# MainBoardSchematic.net
KiCad netlist of a schematic drawn in EAGLE
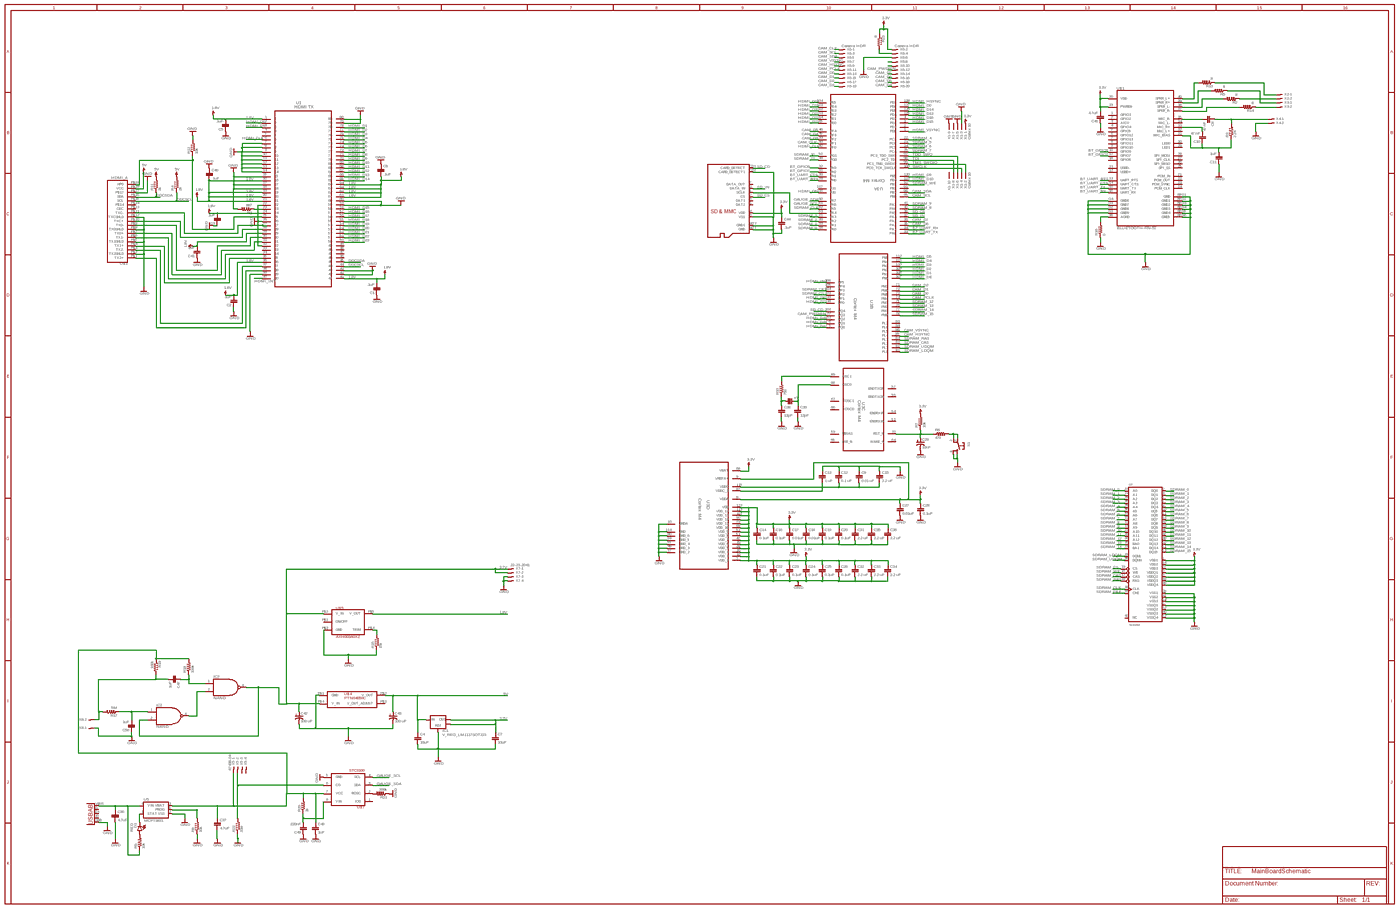
[diagram p0: schematic, sheet 1, overview]
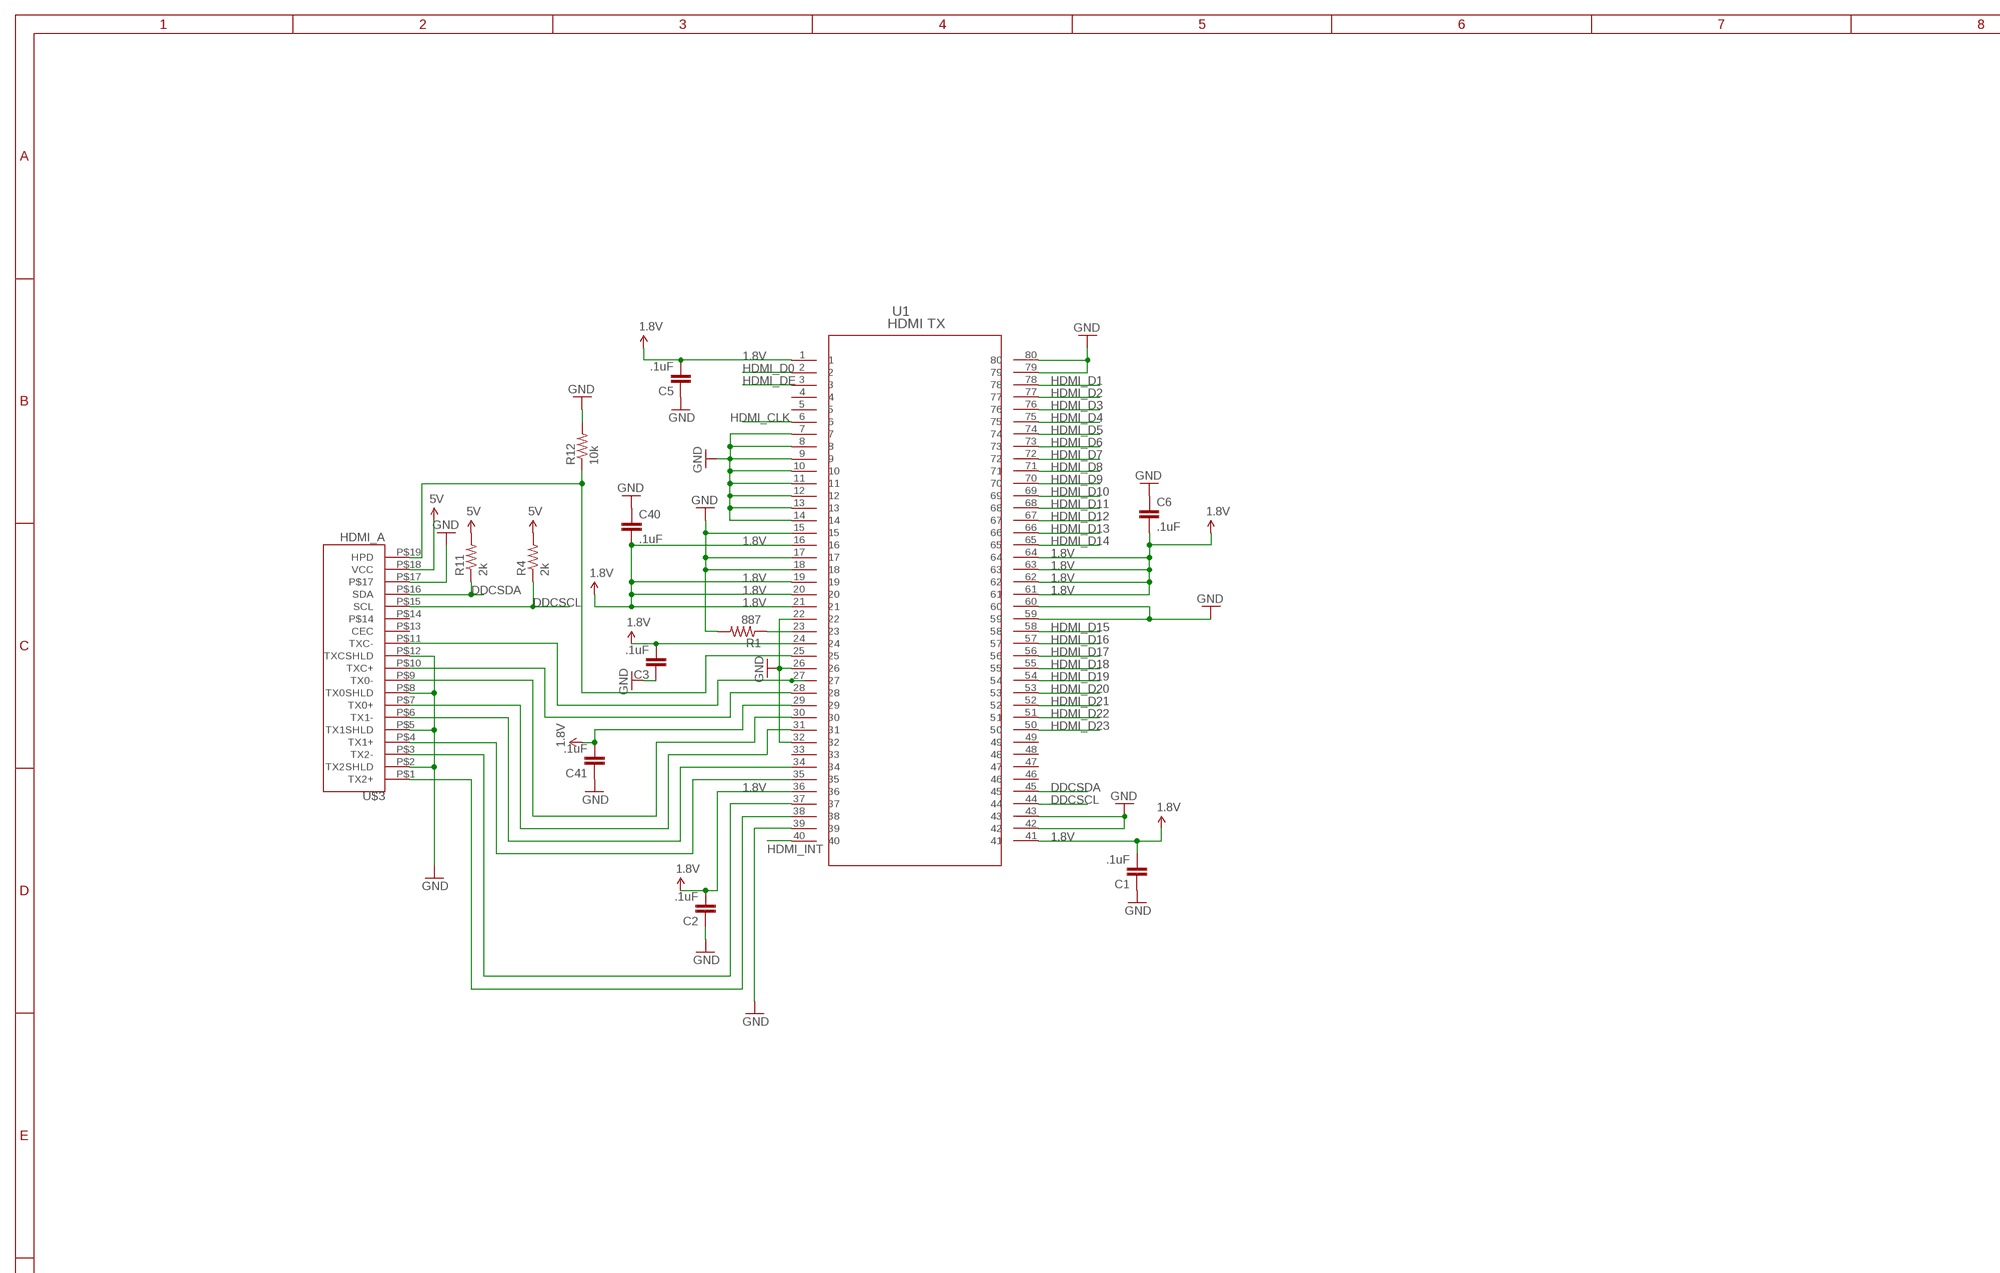
[diagram p1: schematic, sheet 1, part 1 of 4]
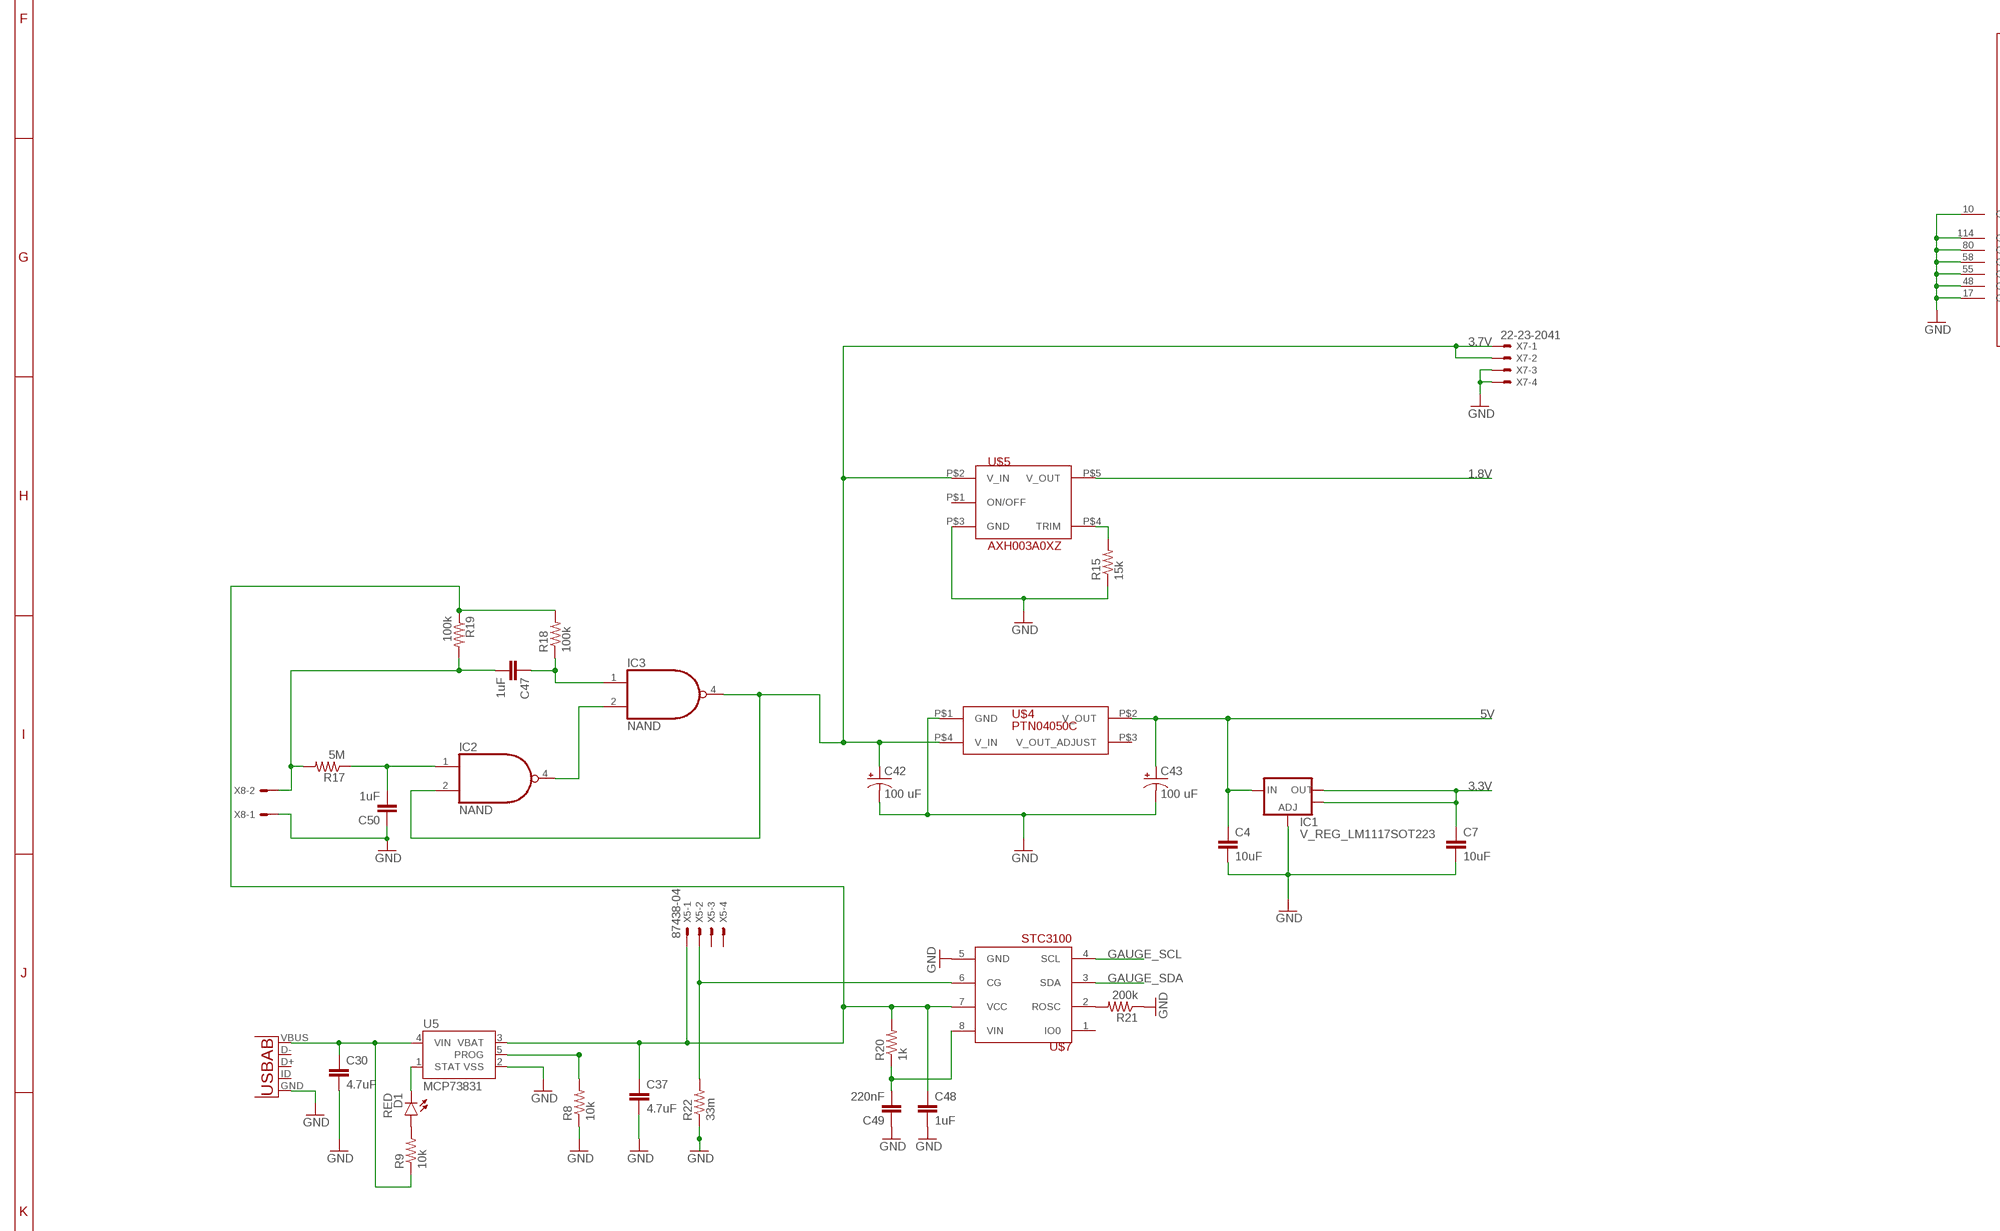
[diagram p2: schematic, sheet 1, part 2 of 4]
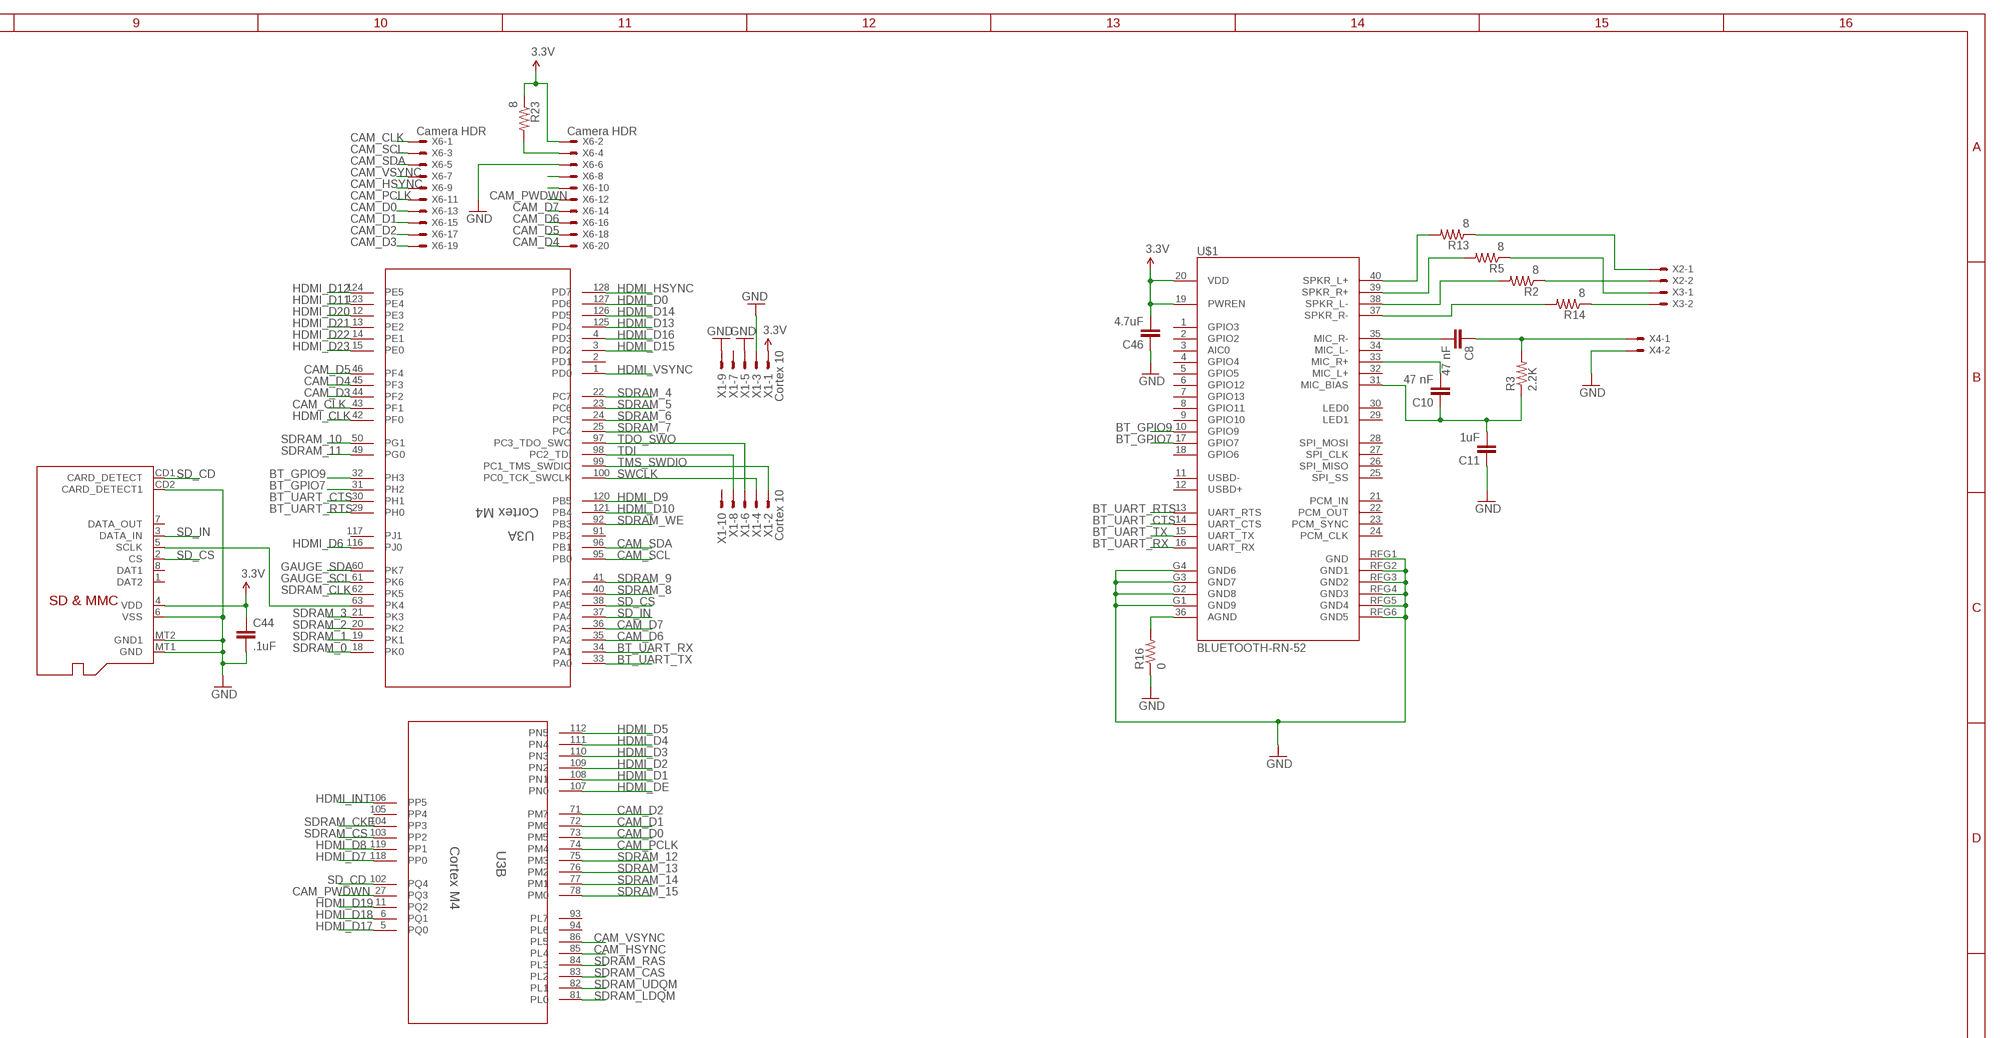
[diagram p3: schematic, sheet 1, part 3 of 4]
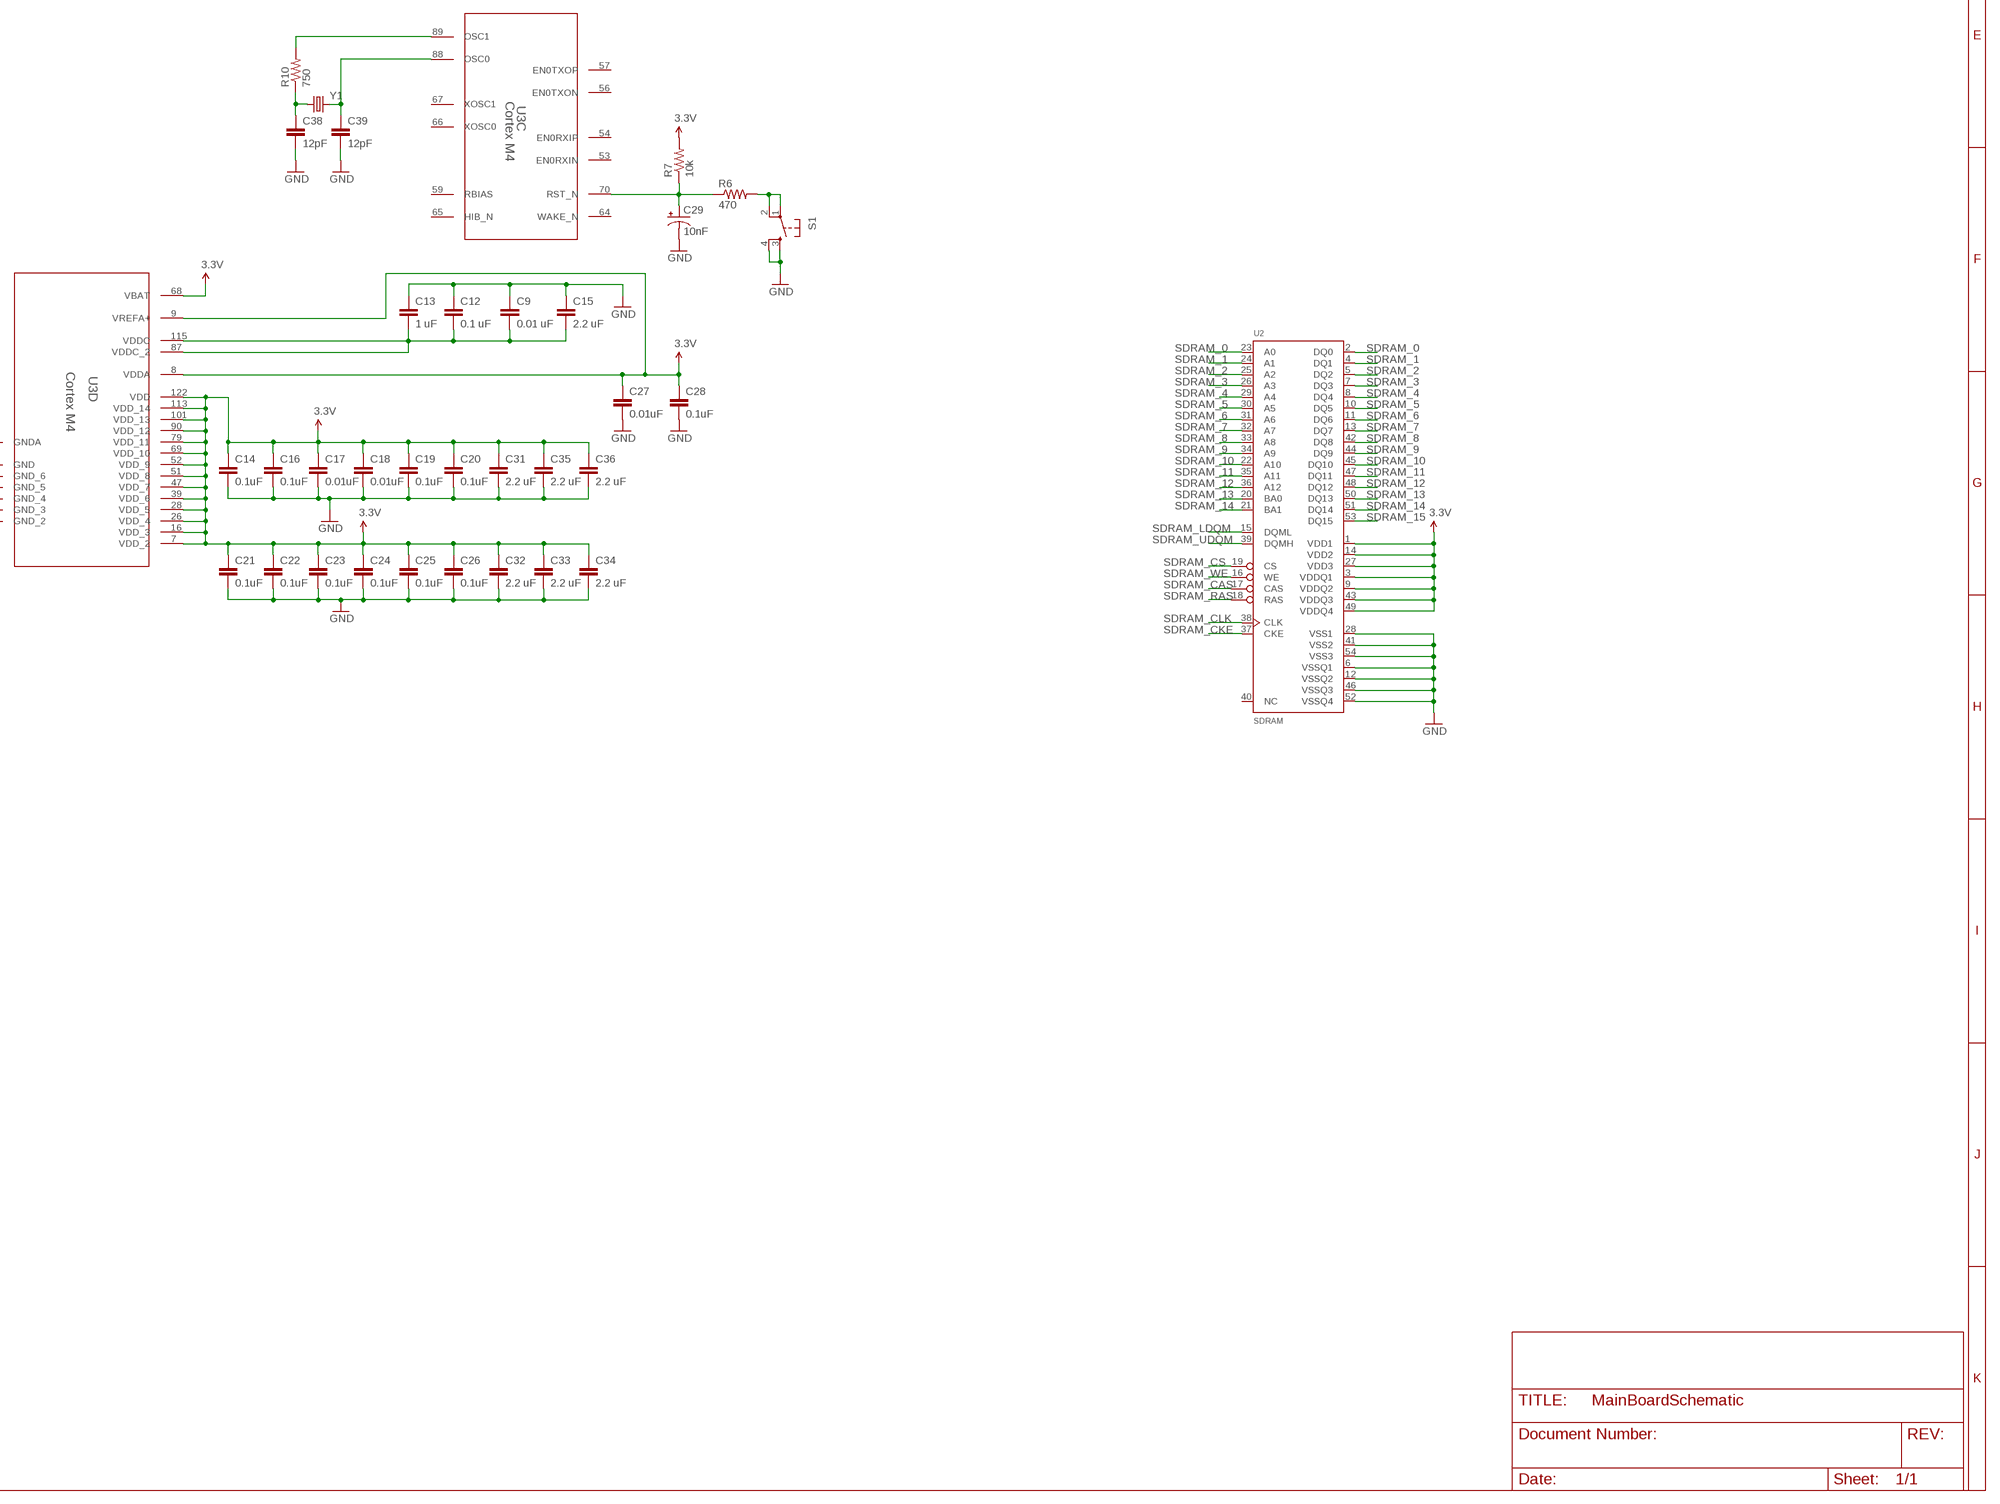
[diagram p4: schematic, sheet 1, part 4 of 4]

(export (version "E")
  (design (tool "Eeschema 10.0.6"))
  (components
    (comp (ref "C1")
      (value ".1uF")
      (footprint "eagle-import:0603-CAP")
      (libsource (lib "eagle-import") (part "CAP0603-CAP"))
    )
    (comp (ref "C2")
      (value ".1uF")
      (footprint "eagle-import:0603-CAP")
      (libsource (lib "eagle-import") (part "CAP0603-CAP"))
    )
    (comp (ref "C3")
      (value ".1uF")
      (footprint "eagle-import:0603-CAP")
      (libsource (lib "eagle-import") (part "CAP0603-CAP"))
    )
    (comp (ref "C4")
      (value "10uF")
      (footprint "eagle-import:0603-CAP")
      (libsource (lib "eagle-import") (part "CAP0603-CAP"))
    )
    (comp (ref "C5")
      (value ".1uF")
      (footprint "eagle-import:0603-CAP")
      (libsource (lib "eagle-import") (part "CAP0603-CAP"))
    )
    (comp (ref "C6")
      (value ".1uF")
      (footprint "eagle-import:0603-CAP")
      (libsource (lib "eagle-import") (part "CAP0603-CAP"))
    )
    (comp (ref "C7")
      (value "10uF")
      (footprint "eagle-import:0603-CAP")
      (libsource (lib "eagle-import") (part "CAP0603-CAP"))
    )
    (comp (ref "C8")
      (value "47 nF")
      (footprint "eagle-import:0603-CAP")
      (libsource (lib "eagle-import") (part "CAP0603-CAP"))
    )
    (comp (ref "C9")
      (value "0.01 uF")
      (footprint "eagle-import:0603-CAP")
      (libsource (lib "eagle-import") (part "CAP0603-CAP"))
    )
    (comp (ref "C10")
      (value "47 nF")
      (footprint "eagle-import:0603-CAP")
      (libsource (lib "eagle-import") (part "CAP0603-CAP"))
    )
    (comp (ref "C11")
      (value "1uF")
      (footprint "eagle-import:0603-CAP")
      (libsource (lib "eagle-import") (part "CAP0603-CAP"))
    )
    (comp (ref "C12")
      (value "0.1 uF")
      (footprint "eagle-import:0603-CAP")
      (libsource (lib "eagle-import") (part "CAP0603-CAP"))
    )
    (comp (ref "C13")
      (value "1 uF")
      (footprint "eagle-import:0603-CAP")
      (libsource (lib "eagle-import") (part "CAP0603-CAP"))
    )
    (comp (ref "C14")
      (value "0.1uF")
      (footprint "eagle-import:0603-CAP")
      (libsource (lib "eagle-import") (part "CAP0603-CAP"))
    )
    (comp (ref "C15")
      (value "2.2 uF")
      (footprint "eagle-import:0603-CAP")
      (libsource (lib "eagle-import") (part "CAP0603-CAP"))
    )
    (comp (ref "C16")
      (value "0.1uF")
      (footprint "eagle-import:0603-CAP")
      (libsource (lib "eagle-import") (part "CAP0603-CAP"))
    )
    (comp (ref "C17")
      (value "0.01uF")
      (footprint "eagle-import:0603-CAP")
      (libsource (lib "eagle-import") (part "CAP0603-CAP"))
    )
    (comp (ref "C18")
      (value "0.01uF")
      (footprint "eagle-import:0603-CAP")
      (libsource (lib "eagle-import") (part "CAP0603-CAP"))
    )
    (comp (ref "C19")
      (value "0.1uF")
      (footprint "eagle-import:0603-CAP")
      (libsource (lib "eagle-import") (part "CAP0603-CAP"))
    )
    (comp (ref "C20")
      (value "0.1uF")
      (footprint "eagle-import:0603-CAP")
      (libsource (lib "eagle-import") (part "CAP0603-CAP"))
    )
    (comp (ref "C21")
      (value "0.1uF")
      (footprint "eagle-import:0603-CAP")
      (libsource (lib "eagle-import") (part "CAP0603-CAP"))
    )
    (comp (ref "C22")
      (value "0.1uF")
      (footprint "eagle-import:0603-CAP")
      (libsource (lib "eagle-import") (part "CAP0603-CAP"))
    )
    (comp (ref "C23")
      (value "0.1uF")
      (footprint "eagle-import:0603-CAP")
      (libsource (lib "eagle-import") (part "CAP0603-CAP"))
    )
    (comp (ref "C24")
      (value "0.1uF")
      (footprint "eagle-import:0603-CAP")
      (libsource (lib "eagle-import") (part "CAP0603-CAP"))
    )
    (comp (ref "C25")
      (value "0.1uF")
      (footprint "eagle-import:0603-CAP")
      (libsource (lib "eagle-import") (part "CAP0603-CAP"))
    )
    (comp (ref "C26")
      (value "0.1uF")
      (footprint "eagle-import:0603-CAP")
      (libsource (lib "eagle-import") (part "CAP0603-CAP"))
    )
    (comp (ref "C27")
      (value "0.01uF")
      (footprint "eagle-import:0603-CAP")
      (libsource (lib "eagle-import") (part "CAP0603-CAP"))
    )
    (comp (ref "C28")
      (value "0.1uF")
      (footprint "eagle-import:0603-CAP")
      (libsource (lib "eagle-import") (part "CAP0603-CAP"))
    )
    (comp (ref "C29")
      (value "10nF")
      (footprint "eagle-import:EIA6032")
      (libsource (lib "eagle-import") (part "SparkFun-Passives_CAP_POL6032"))
    )
    (comp (ref "C30")
      (value "4.7uF")
      (footprint "eagle-import:0603-CAP")
      (libsource (lib "eagle-import") (part "CAP0603-CAP"))
    )
    (comp (ref "C31")
      (value "2.2 uF")
      (footprint "eagle-import:0603-CAP")
      (libsource (lib "eagle-import") (part "CAP0603-CAP"))
    )
    (comp (ref "C32")
      (value "2.2 uF")
      (footprint "eagle-import:0603-CAP")
      (libsource (lib "eagle-import") (part "CAP0603-CAP"))
    )
    (comp (ref "C33")
      (value "2.2 uF")
      (footprint "eagle-import:0603-CAP")
      (libsource (lib "eagle-import") (part "CAP0603-CAP"))
    )
    (comp (ref "C34")
      (value "2.2 uF")
      (footprint "eagle-import:0603-CAP")
      (libsource (lib "eagle-import") (part "CAP0603-CAP"))
    )
    (comp (ref "C35")
      (value "2.2 uF")
      (footprint "eagle-import:0603-CAP")
      (libsource (lib "eagle-import") (part "CAP0603-CAP"))
    )
    (comp (ref "C36")
      (value "2.2 uF")
      (footprint "eagle-import:0603-CAP")
      (libsource (lib "eagle-import") (part "CAP0603-CAP"))
    )
    (comp (ref "C37")
      (value "4.7uF")
      (footprint "eagle-import:0603-CAP")
      (libsource (lib "eagle-import") (part "CAP0603-CAP"))
    )
    (comp (ref "C38")
      (value "12pF")
      (footprint "eagle-import:0603-CAP")
      (libsource (lib "eagle-import") (part "CAP0603-CAP"))
    )
    (comp (ref "C39")
      (value "12pF")
      (footprint "eagle-import:0603-CAP")
      (libsource (lib "eagle-import") (part "CAP0603-CAP"))
    )
    (comp (ref "C40")
      (value ".1uF")
      (footprint "eagle-import:0603-CAP")
      (libsource (lib "eagle-import") (part "CAP0603-CAP"))
    )
    (comp (ref "C41")
      (value ".1uF")
      (footprint "eagle-import:0603-CAP")
      (libsource (lib "eagle-import") (part "CAP0603-CAP"))
    )
    (comp (ref "C42")
      (value "100 uF")
      (footprint "eagle-import:EIA6032")
      (libsource (lib "eagle-import") (part "CAP_POL6032"))
    )
    (comp (ref "C43")
      (value "100 uF")
      (footprint "eagle-import:EIA6032")
      (libsource (lib "eagle-import") (part "CAP_POL6032"))
    )
    (comp (ref "C44")
      (value ".1uF")
      (footprint "eagle-import:0603-CAP")
      (libsource (lib "eagle-import") (part "CAP0603-CAP"))
    )
    (comp (ref "C46")
      (value "4.7uF")
      (footprint "eagle-import:0603-CAP")
      (libsource (lib "eagle-import") (part "CAP0603-CAP"))
    )
    (comp (ref "C47")
      (value "1uF")
      (footprint "eagle-import:0603-CAP")
      (libsource (lib "eagle-import") (part "CAP0603-CAP"))
    )
    (comp (ref "C48")
      (value "1uF")
      (footprint "eagle-import:0603-CAP")
      (libsource (lib "eagle-import") (part "CAP0603-CAP"))
    )
    (comp (ref "C49")
      (value "220nF")
      (footprint "eagle-import:0603-CAP")
      (libsource (lib "eagle-import") (part "CAP0603-CAP"))
    )
    (comp (ref "C50")
      (value "1uF")
      (footprint "eagle-import:0603-CAP")
      (libsource (lib "eagle-import") (part "CAP0603-CAP"))
    )
    (comp (ref "D1")
      (value "RED")
      (footprint "eagle-import:LED-0603")
      (libsource (lib "eagle-import") (part "LED-RED0603"))
    )
    (comp (ref "IC1")
      (value "V_REG_LM1117SOT223")
      (footprint "eagle-import:SOT223")
      (libsource (lib "eagle-import") (part "V_REG_LM1117SOT223"))
    )
    (comp (ref "IC2")
      (value "NAND")
      (footprint "eagle-import:SOT23-5")
      (libsource (lib "eagle-import") (part "741G00DBVAHC"))
    )
    (comp (ref "IC3")
      (value "NAND")
      (footprint "eagle-import:SOT23-5")
      (libsource (lib "eagle-import") (part "741G00DBVAHC"))
    )
    (comp (ref "R1")
      (value "887")
      (footprint "eagle-import:0603-RES")
      (libsource (lib "eagle-import") (part "RESISTOR0603-RES"))
    )
    (comp (ref "R2")
      (value "8")
      (footprint "eagle-import:1206")
      (libsource (lib "eagle-import") (part "RESISTOR1206"))
    )
    (comp (ref "R3")
      (value "2.2K")
      (footprint "eagle-import:1206")
      (libsource (lib "eagle-import") (part "RESISTOR1206"))
    )
    (comp (ref "R4")
      (value "2k")
      (footprint "eagle-import:0603-RES")
      (libsource (lib "eagle-import") (part "RESISTOR0603-RES"))
    )
    (comp (ref "R5")
      (value "8")
      (footprint "eagle-import:1206")
      (libsource (lib "eagle-import") (part "RESISTOR1206"))
    )
    (comp (ref "R6")
      (value "470")
      (footprint "eagle-import:0603-RES")
      (libsource (lib "eagle-import") (part "RESISTOR0603-RES"))
    )
    (comp (ref "R7")
      (value "10k")
      (footprint "eagle-import:0603-RES")
      (libsource (lib "eagle-import") (part "RESISTOR0603-RES"))
    )
    (comp (ref "R8")
      (value "10k")
      (footprint "eagle-import:0603-RES")
      (libsource (lib "eagle-import") (part "RESISTOR0603-RES"))
    )
    (comp (ref "R9")
      (value "10k")
      (footprint "eagle-import:0603-RES")
      (libsource (lib "eagle-import") (part "RESISTOR0603-RES"))
    )
    (comp (ref "R10")
      (value "750")
      (footprint "eagle-import:0603-RES")
      (libsource (lib "eagle-import") (part "RESISTOR0603-RES"))
    )
    (comp (ref "R11")
      (value "2k")
      (footprint "eagle-import:0603-RES")
      (libsource (lib "eagle-import") (part "RESISTOR0603-RES"))
    )
    (comp (ref "R12")
      (value "10k")
      (footprint "eagle-import:0603-RES")
      (libsource (lib "eagle-import") (part "RESISTOR0603-RES"))
    )
    (comp (ref "R13")
      (value "8")
      (footprint "eagle-import:1206")
      (libsource (lib "eagle-import") (part "RESISTOR1206"))
    )
    (comp (ref "R14")
      (value "8")
      (footprint "eagle-import:1206")
      (libsource (lib "eagle-import") (part "RESISTOR1206"))
    )
    (comp (ref "R15")
      (value "15k")
      (footprint "eagle-import:0603-RES")
      (libsource (lib "eagle-import") (part "RESISTOR0603-RES"))
    )
    (comp (ref "R16")
      (value "0")
      (footprint "eagle-import:1206")
      (libsource (lib "eagle-import") (part "RESISTOR1206"))
    )
    (comp (ref "R17")
      (value "5M")
      (footprint "eagle-import:0603-RES")
      (libsource (lib "eagle-import") (part "RESISTOR0603-RES"))
    )
    (comp (ref "R18")
      (value "100k")
      (footprint "eagle-import:0603-RES")
      (libsource (lib "eagle-import") (part "RESISTOR0603-RES"))
    )
    (comp (ref "R19")
      (value "100k")
      (footprint "eagle-import:0603-RES")
      (libsource (lib "eagle-import") (part "RESISTOR0603-RES"))
    )
    (comp (ref "R20")
      (value "1k")
      (footprint "eagle-import:0603-RES")
      (libsource (lib "eagle-import") (part "RESISTOR0603-RES"))
    )
    (comp (ref "R21")
      (value "200k")
      (footprint "eagle-import:0603-RES")
      (libsource (lib "eagle-import") (part "RESISTOR0603-RES"))
    )
    (comp (ref "R22")
      (value "33m")
      (footprint "eagle-import:0603-RES")
      (libsource (lib "eagle-import") (part "RESISTOR0603-RES"))
    )
    (comp (ref "R23")
      (value "8")
      (footprint "eagle-import:1206")
      (libsource (lib "eagle-import") (part "RESISTOR1206"))
    )
    (comp (ref "S1")
      (value "TAC_SWITCHPTH")
      (footprint "eagle-import:TACTILE-PTH")
      (libsource (lib "eagle-import") (part "TAC_SWITCHPTH"))
    )
    (comp (ref "U$1")
      (value "BLUETOOTH-RN-52")
      (footprint "eagle-import:RN-52")
      (libsource (lib "eagle-import") (part "BLUETOOTH-RN-52"))
    )
    (comp (ref "U$2")
      (value "MICROSD")
      (footprint "eagle-import:MICROSD")
      (libsource (lib "eagle-import") (part "MICROSD"))
    )
    (comp (ref "U$3")
      (value "HDMI_A")
      (footprint "eagle-import:HDMI_A_SMD")
      (libsource (lib "eagle-import") (part "HDMI_A"))
    )
    (comp (ref "U$4")
      (value "PTN04050C")
      (footprint "eagle-import:PTN04050C")
      (libsource (lib "eagle-import") (part "PTN04050C"))
    )
    (comp (ref "U$5")
      (value "AXH003A0XZ")
      (footprint "eagle-import:AXH003A0XZ")
      (libsource (lib "eagle-import") (part "AXH003A0XZ"))
    )
    (comp (ref "U$7")
      (value "STC3100")
      (footprint "eagle-import:MSOP8")
      (libsource (lib "eagle-import") (part "STC3100"))
    )
    (comp (ref "U1")
      (value "HDMI TX")
      (footprint "eagle-import:ST_80_2")
      (libsource (lib "eagle-import") (part "AD9389BBSTZ-165"))
    )
    (comp (ref "U2")
      (value "SDRAM")
      (footprint "eagle-import:TSOP54-400")
      (libsource (lib "eagle-import") (part "SDRAM_54TSOP"))
    )
    (comp (ref "U3")
      (value "Cortex M4")
      (footprint "eagle-import:PDT0128A_N")
      (fields
        (field (name "ALTERNATEPARTNUMBER") "TM4C129ENCPDTI3")
        (field (name "MANUFACTURER") "Texas Instruments")
        (field (name "PARTNUMBER") "TM4C129ENCPDTI3R")
      )
      (libsource (lib "eagle-import") (part "TM4C129ENCPDTI3R"))
    )
    (comp (ref "U4")
      (value "USB-AB")
      (footprint "eagle-import:USB-AB-MICRO-SMD")
      (libsource (lib "eagle-import") (part "USB-AB"))
    )
    (comp (ref "U5")
      (value "MCP73831")
      (footprint "eagle-import:SOT23-5")
      (libsource (lib "eagle-import") (part "MCP73831"))
    )
    (comp (ref "X1")
      (value "Cortex 10")
      (footprint "eagle-import:1365-10")
      (libsource (lib "eagle-import") (part "1365-10"))
    )
    (comp (ref "X2")
      (value "KK-156-2")
      (footprint "eagle-import:KK-156-2")
      (libsource (lib "eagle-import") (part "KK-156-2"))
    )
    (comp (ref "X3")
      (value "KK-156-2")
      (footprint "eagle-import:KK-156-2")
      (libsource (lib "eagle-import") (part "KK-156-2"))
    )
    (comp (ref "X4")
      (value "KK-156-2")
      (footprint "eagle-import:KK-156-2")
      (libsource (lib "eagle-import") (part "KK-156-2"))
    )
    (comp (ref "X5")
      (value "87438-04")
      (footprint "eagle-import:87438-04")
      (libsource (lib "eagle-import") (part "87438-04"))
    )
    (comp (ref "X6")
      (value "Camera HDR")
      (footprint "eagle-import:87758-2016")
      (fields (field (name "MPN") "87758-2016"))
      (libsource (lib "eagle-import") (part "87758-2016"))
    )
    (comp (ref "X7")
      (value "22-23-2041")
      (footprint "eagle-import:22-23-2041")
      (fields (field (name "MF") "MOLEX"))
      (libsource (lib "eagle-import") (part "22-23-2041"))
    )
    (comp (ref "X8")
      (value "KK-156-2")
      (footprint "eagle-import:KK-156-2")
      (libsource (lib "eagle-import") (part "KK-156-2"))
    )
    (comp (ref "Y1")
      (value "CRYSTAL")
      (footprint "eagle-import:NX5032GA")
      (libsource (lib "eagle-import") (part "CRYSTAL"))
    )
  )
  (nets
    (net (code "1") (name "/3.7V") (class "Default")
      (node (ref "C42") (pin "P$1") (pinfunction "+_P$1") (pintype "passive"))
      (node (ref "IC2") (pin "2") (pinfunction "I1_2") (pintype "input"))
      (node (ref "IC3") (pin "4") (pinfunction "O_4") (pintype "output"))
      (node (ref "U$4") (pin "P$4") (pinfunction "V_IN_P$4") (pintype "bidirectional"))
      (node (ref "U$5") (pin "P$2") (pinfunction "V_IN_P$2") (pintype "bidirectional"))
      (node (ref "X7") (pin "1") (pinfunction "S_1") (pintype "passive"))
      (node (ref "X7") (pin "2") (pinfunction "S_2") (pintype "passive"))
    )
    (net (code "2") (name "/BT_GPIO7") (class "Default")
      (node (ref "U$1") (pin "17") (pinfunction "GPIO7_17") (pintype "bidirectional"))
      (node (ref "U3") (pin "31") (pinfunction "PH2_31") (pintype "bidirectional"))
    )
    (net (code "3") (name "/BT_GPIO9") (class "Default")
      (node (ref "U$1") (pin "10") (pinfunction "GPIO9_10") (pintype "bidirectional"))
      (node (ref "U3") (pin "32") (pinfunction "PH3_32") (pintype "bidirectional"))
    )
    (net (code "4") (name "/BT_UART_CTS") (class "Default")
      (node (ref "U$1") (pin "14") (pinfunction "UART_CTS_14") (pintype "bidirectional"))
      (node (ref "U3") (pin "30") (pinfunction "PH1_30") (pintype "bidirectional"))
    )
    (net (code "5") (name "/BT_UART_RTS") (class "Default")
      (node (ref "U$1") (pin "13") (pinfunction "UART_RTS_13") (pintype "bidirectional"))
      (node (ref "U3") (pin "29") (pinfunction "PH0_29") (pintype "bidirectional"))
    )
    (net (code "6") (name "/BT_UART_RX") (class "Default")
      (node (ref "U$1") (pin "16") (pinfunction "UART_RX_16") (pintype "bidirectional"))
      (node (ref "U3") (pin "34") (pinfunction "PA1_34") (pintype "bidirectional"))
    )
    (net (code "7") (name "/BT_UART_TX") (class "Default")
      (node (ref "U$1") (pin "15") (pinfunction "UART_TX_15") (pintype "bidirectional"))
      (node (ref "U3") (pin "33") (pinfunction "PA0_33") (pintype "bidirectional"))
    )
    (net (code "8") (name "/CAM_CLK") (class "Default")
      (node (ref "U3") (pin "43") (pinfunction "PF1_43") (pintype "bidirectional"))
      (node (ref "X6") (pin "1") (pinfunction "S_1") (pintype "passive"))
    )
    (net (code "9") (name "/CAM_D0") (class "Default")
      (node (ref "U3") (pin "73") (pinfunction "PM5_73") (pintype "bidirectional"))
      (node (ref "X6") (pin "13") (pinfunction "S_13") (pintype "passive"))
    )
    (net (code "10") (name "/CAM_D1") (class "Default")
      (node (ref "U3") (pin "72") (pinfunction "PM6_72") (pintype "bidirectional"))
      (node (ref "X6") (pin "15") (pinfunction "S_15") (pintype "passive"))
    )
    (net (code "11") (name "/CAM_D2") (class "Default")
      (node (ref "U3") (pin "71") (pinfunction "PM7_71") (pintype "bidirectional"))
      (node (ref "X6") (pin "17") (pinfunction "S_17") (pintype "passive"))
    )
    (net (code "12") (name "/CAM_D3") (class "Default")
      (node (ref "U3") (pin "44") (pinfunction "PF2_44") (pintype "bidirectional"))
      (node (ref "X6") (pin "19") (pinfunction "S_19") (pintype "passive"))
    )
    (net (code "13") (name "/CAM_D4") (class "Default")
      (node (ref "U3") (pin "45") (pinfunction "PF3_45") (pintype "bidirectional"))
      (node (ref "X6") (pin "20") (pinfunction "S_20") (pintype "passive"))
    )
    (net (code "14") (name "/CAM_D5") (class "Default")
      (node (ref "U3") (pin "46") (pinfunction "PF4_46") (pintype "bidirectional"))
      (node (ref "X6") (pin "18") (pinfunction "S_18") (pintype "passive"))
    )
    (net (code "15") (name "/CAM_D6") (class "Default")
      (node (ref "U3") (pin "35") (pinfunction "PA2_35") (pintype "bidirectional"))
      (node (ref "X6") (pin "16") (pinfunction "S_16") (pintype "passive"))
    )
    (net (code "16") (name "/CAM_D7") (class "Default")
      (node (ref "U3") (pin "36") (pinfunction "PA3_36") (pintype "bidirectional"))
      (node (ref "X6") (pin "14") (pinfunction "S_14") (pintype "passive"))
    )
    (net (code "17") (name "/CAM_HSYNC") (class "Default")
      (node (ref "U3") (pin "85") (pinfunction "PL4_85") (pintype "bidirectional"))
      (node (ref "X6") (pin "9") (pinfunction "S_9") (pintype "passive"))
    )
    (net (code "18") (name "/CAM_PCLK") (class "Default")
      (node (ref "U3") (pin "74") (pinfunction "PM4_74") (pintype "bidirectional"))
      (node (ref "X6") (pin "11") (pinfunction "S_11") (pintype "passive"))
    )
    (net (code "19") (name "/CAM_PWDWN") (class "Default")
      (node (ref "U3") (pin "27") (pinfunction "PQ3_27") (pintype "bidirectional"))
      (node (ref "X6") (pin "12") (pinfunction "S_12") (pintype "passive"))
    )
    (net (code "20") (name "/CAM_SCL") (class "Default")
      (node (ref "U3") (pin "95") (pinfunction "PB0_95") (pintype "bidirectional"))
      (node (ref "X6") (pin "3") (pinfunction "S_3") (pintype "passive"))
    )
    (net (code "21") (name "/CAM_SDA") (class "Default")
      (node (ref "U3") (pin "96") (pinfunction "PB1_96") (pintype "bidirectional"))
      (node (ref "X6") (pin "5") (pinfunction "S_5") (pintype "passive"))
    )
    (net (code "22") (name "/CAM_VSYNC") (class "Default")
      (node (ref "U3") (pin "86") (pinfunction "PL5_86") (pintype "bidirectional"))
      (node (ref "X6") (pin "7") (pinfunction "S_7") (pintype "passive"))
    )
    (net (code "23") (name "/DDCSCL") (class "Default")
      (node (ref "R4") (pin "1") (pinfunction "1_1") (pintype "passive"))
      (node (ref "U$3") (pin "P$15") (pinfunction "SCL_P$15") (pintype "bidirectional"))
      (node (ref "U1") (pin "44") (pinfunction "44_44") (pintype "passive"))
    )
    (net (code "24") (name "/DDCSDA") (class "Default")
      (node (ref "R11") (pin "1") (pinfunction "1_1") (pintype "passive"))
      (node (ref "U$3") (pin "P$16") (pinfunction "SDA_P$16") (pintype "bidirectional"))
      (node (ref "U1") (pin "45") (pinfunction "45_45") (pintype "passive"))
    )
    (net (code "25") (name "/GAUGE_SCL") (class "Default")
      (node (ref "U$7") (pin "4") (pinfunction "SCL_4") (pintype "bidirectional"))
      (node (ref "U3") (pin "61") (pinfunction "PK6_61") (pintype "bidirectional"))
    )
    (net (code "26") (name "/GAUGE_SDA") (class "Default")
      (node (ref "U$7") (pin "3") (pinfunction "SDA_3") (pintype "bidirectional"))
      (node (ref "U3") (pin "60") (pinfunction "PK7_60") (pintype "bidirectional"))
    )
    (net (code "27") (name "/HDMI_CLK") (class "Default")
      (node (ref "U1") (pin "6") (pinfunction "6_6") (pintype "passive"))
      (node (ref "U3") (pin "42") (pinfunction "PF0_42") (pintype "bidirectional"))
    )
    (net (code "28") (name "/HDMI_D0") (class "Default")
      (node (ref "U1") (pin "2") (pinfunction "2_2") (pintype "passive"))
      (node (ref "U3") (pin "127") (pinfunction "PD6_127") (pintype "bidirectional"))
    )
    (net (code "29") (name "/HDMI_D1") (class "Default")
      (node (ref "U1") (pin "78") (pinfunction "78_78") (pintype "passive"))
      (node (ref "U3") (pin "108") (pinfunction "PN1_108") (pintype "bidirectional"))
    )
    (net (code "30") (name "/HDMI_D2") (class "Default")
      (node (ref "U1") (pin "77") (pinfunction "77_77") (pintype "passive"))
      (node (ref "U3") (pin "109") (pinfunction "PN2_109") (pintype "bidirectional"))
    )
    (net (code "31") (name "/HDMI_D3") (class "Default")
      (node (ref "U1") (pin "76") (pinfunction "76_76") (pintype "passive"))
      (node (ref "U3") (pin "110") (pinfunction "PN3_110") (pintype "bidirectional"))
    )
    (net (code "32") (name "/HDMI_D4") (class "Default")
      (node (ref "U1") (pin "75") (pinfunction "75_75") (pintype "passive"))
      (node (ref "U3") (pin "111") (pinfunction "PN4_111") (pintype "bidirectional"))
    )
    (net (code "33") (name "/HDMI_D5") (class "Default")
      (node (ref "U1") (pin "74") (pinfunction "74_74") (pintype "passive"))
      (node (ref "U3") (pin "112") (pinfunction "PN5_112") (pintype "bidirectional"))
    )
    (net (code "34") (name "/HDMI_D6") (class "Default")
      (node (ref "U1") (pin "73") (pinfunction "73_73") (pintype "passive"))
      (node (ref "U3") (pin "116") (pinfunction "PJ0_116") (pintype "bidirectional"))
    )
    (net (code "35") (name "/HDMI_D7") (class "Default")
      (node (ref "U1") (pin "72") (pinfunction "72_72") (pintype "passive"))
      (node (ref "U3") (pin "118") (pinfunction "PP0_118") (pintype "bidirectional"))
    )
    (net (code "36") (name "/HDMI_D8") (class "Default")
      (node (ref "U1") (pin "71") (pinfunction "71_71") (pintype "passive"))
      (node (ref "U3") (pin "119") (pinfunction "PP1_119") (pintype "bidirectional"))
    )
    (net (code "37") (name "/HDMI_D9") (class "Default")
      (node (ref "U1") (pin "70") (pinfunction "70_70") (pintype "passive"))
      (node (ref "U3") (pin "120") (pinfunction "PB5_120") (pintype "bidirectional"))
    )
    (net (code "38") (name "/HDMI_D10") (class "Default")
      (node (ref "U1") (pin "69") (pinfunction "69_69") (pintype "passive"))
      (node (ref "U3") (pin "121") (pinfunction "PB4_121") (pintype "bidirectional"))
    )
    (net (code "39") (name "/HDMI_D11") (class "Default")
      (node (ref "U1") (pin "68") (pinfunction "68_68") (pintype "passive"))
      (node (ref "U3") (pin "123") (pinfunction "PE4_123") (pintype "bidirectional"))
    )
    (net (code "40") (name "/HDMI_D12") (class "Default")
      (node (ref "U1") (pin "67") (pinfunction "67_67") (pintype "passive"))
      (node (ref "U3") (pin "124") (pinfunction "PE5_124") (pintype "bidirectional"))
    )
    (net (code "41") (name "/HDMI_D13") (class "Default")
      (node (ref "U1") (pin "66") (pinfunction "66_66") (pintype "passive"))
      (node (ref "U3") (pin "125") (pinfunction "PD4_125") (pintype "bidirectional"))
    )
    (net (code "42") (name "/HDMI_D14") (class "Default")
      (node (ref "U1") (pin "65") (pinfunction "65_65") (pintype "passive"))
      (node (ref "U3") (pin "126") (pinfunction "PD5_126") (pintype "bidirectional"))
    )
    (net (code "43") (name "/HDMI_D15") (class "Default")
      (node (ref "U1") (pin "58") (pinfunction "58_58") (pintype "passive"))
      (node (ref "U3") (pin "3") (pinfunction "PD2_3") (pintype "bidirectional"))
    )
    (net (code "44") (name "/HDMI_D16") (class "Default")
      (node (ref "U1") (pin "57") (pinfunction "57_57") (pintype "passive"))
      (node (ref "U3") (pin "4") (pinfunction "PD3_4") (pintype "bidirectional"))
    )
    (net (code "45") (name "/HDMI_D17") (class "Default")
      (node (ref "U1") (pin "56") (pinfunction "56_56") (pintype "passive"))
      (node (ref "U3") (pin "5") (pinfunction "PQ0_5") (pintype "bidirectional"))
    )
    (net (code "46") (name "/HDMI_D18") (class "Default")
      (node (ref "U1") (pin "55") (pinfunction "55_55") (pintype "passive"))
      (node (ref "U3") (pin "6") (pinfunction "PQ1_6") (pintype "bidirectional"))
    )
    (net (code "47") (name "/HDMI_D19") (class "Default")
      (node (ref "U1") (pin "54") (pinfunction "54_54") (pintype "passive"))
      (node (ref "U3") (pin "11") (pinfunction "PQ2_11") (pintype "bidirectional"))
    )
    (net (code "48") (name "/HDMI_D20") (class "Default")
      (node (ref "U1") (pin "53") (pinfunction "53_53") (pintype "passive"))
      (node (ref "U3") (pin "12") (pinfunction "PE3_12") (pintype "bidirectional"))
    )
    (net (code "49") (name "/HDMI_D21") (class "Default")
      (node (ref "U1") (pin "52") (pinfunction "52_52") (pintype "passive"))
      (node (ref "U3") (pin "13") (pinfunction "PE2_13") (pintype "bidirectional"))
    )
    (net (code "50") (name "/HDMI_D22") (class "Default")
      (node (ref "U1") (pin "51") (pinfunction "51_51") (pintype "passive"))
      (node (ref "U3") (pin "14") (pinfunction "PE1_14") (pintype "bidirectional"))
    )
    (net (code "51") (name "/HDMI_D23") (class "Default")
      (node (ref "U1") (pin "50") (pinfunction "50_50") (pintype "passive"))
      (node (ref "U3") (pin "15") (pinfunction "PE0_15") (pintype "bidirectional"))
    )
    (net (code "52") (name "/HDMI_DE") (class "Default")
      (node (ref "U1") (pin "3") (pinfunction "3_3") (pintype "passive"))
      (node (ref "U3") (pin "107") (pinfunction "PN0_107") (pintype "bidirectional"))
    )
    (net (code "53") (name "/HDMI_HSYNC") (class "Default")
      (node (ref "U3") (pin "128") (pinfunction "PD7_128") (pintype "bidirectional"))
    )
    (net (code "54") (name "/HDMI_INT") (class "Default")
      (node (ref "U1") (pin "40") (pinfunction "40_40") (pintype "passive"))
      (node (ref "U3") (pin "106") (pinfunction "PP5_106") (pintype "bidirectional"))
    )
    (net (code "55") (name "/HDMI_VSYNC") (class "Default")
      (node (ref "U3") (pin "1") (pinfunction "PD0_1") (pintype "bidirectional"))
    )
    (net (code "56") (name "/SDRAM_0") (class "Default")
      (node (ref "U2") (pin "2") (pinfunction "DQ0_2") (pintype "bidirectional"))
      (node (ref "U2") (pin "23") (pinfunction "A0_23") (pintype "bidirectional"))
      (node (ref "U3") (pin "18") (pinfunction "PK0_18") (pintype "bidirectional"))
    )
    (net (code "57") (name "/SDRAM_1") (class "Default")
      (node (ref "U2") (pin "24") (pinfunction "A1_24") (pintype "bidirectional"))
      (node (ref "U2") (pin "4") (pinfunction "DQ1_4") (pintype "bidirectional"))
      (node (ref "U3") (pin "19") (pinfunction "PK1_19") (pintype "bidirectional"))
    )
    (net (code "58") (name "/SDRAM_2") (class "Default")
      (node (ref "U2") (pin "25") (pinfunction "A2_25") (pintype "bidirectional"))
      (node (ref "U2") (pin "5") (pinfunction "DQ2_5") (pintype "bidirectional"))
      (node (ref "U3") (pin "20") (pinfunction "PK2_20") (pintype "bidirectional"))
    )
    (net (code "59") (name "/SDRAM_3") (class "Default")
      (node (ref "U2") (pin "26") (pinfunction "A3_26") (pintype "bidirectional"))
      (node (ref "U2") (pin "7") (pinfunction "DQ3_7") (pintype "bidirectional"))
      (node (ref "U3") (pin "21") (pinfunction "PK3_21") (pintype "bidirectional"))
    )
    (net (code "60") (name "/SDRAM_4") (class "Default")
      (node (ref "U2") (pin "29") (pinfunction "A4_29") (pintype "bidirectional"))
      (node (ref "U2") (pin "8") (pinfunction "DQ4_8") (pintype "bidirectional"))
      (node (ref "U3") (pin "22") (pinfunction "PC7_22") (pintype "bidirectional"))
    )
    (net (code "61") (name "/SDRAM_5") (class "Default")
      (node (ref "U2") (pin "10") (pinfunction "DQ5_10") (pintype "bidirectional"))
      (node (ref "U2") (pin "30") (pinfunction "A5_30") (pintype "bidirectional"))
      (node (ref "U3") (pin "23") (pinfunction "PC6_23") (pintype "bidirectional"))
    )
    (net (code "62") (name "/SDRAM_6") (class "Default")
      (node (ref "U2") (pin "11") (pinfunction "DQ6_11") (pintype "bidirectional"))
      (node (ref "U2") (pin "31") (pinfunction "A6_31") (pintype "bidirectional"))
      (node (ref "U3") (pin "24") (pinfunction "PC5_24") (pintype "bidirectional"))
    )
    (net (code "63") (name "/SDRAM_7") (class "Default")
      (node (ref "U2") (pin "13") (pinfunction "DQ7_13") (pintype "bidirectional"))
      (node (ref "U2") (pin "32") (pinfunction "A7_32") (pintype "bidirectional"))
      (node (ref "U3") (pin "25") (pinfunction "PC4_25") (pintype "bidirectional"))
    )
    (net (code "64") (name "/SDRAM_8") (class "Default")
      (node (ref "U2") (pin "33") (pinfunction "A8_33") (pintype "bidirectional"))
      (node (ref "U2") (pin "42") (pinfunction "DQ8_42") (pintype "bidirectional"))
      (node (ref "U3") (pin "40") (pinfunction "PA6_40") (pintype "bidirectional"))
    )
    (net (code "65") (name "/SDRAM_9") (class "Default")
      (node (ref "U2") (pin "34") (pinfunction "A9_34") (pintype "bidirectional"))
      (node (ref "U2") (pin "44") (pinfunction "DQ9_44") (pintype "bidirectional"))
      (node (ref "U3") (pin "41") (pinfunction "PA7_41") (pintype "bidirectional"))
    )
    (net (code "66") (name "/SDRAM_10") (class "Default")
      (node (ref "U2") (pin "22") (pinfunction "A10_22") (pintype "bidirectional"))
      (node (ref "U2") (pin "45") (pinfunction "DQ10_45") (pintype "bidirectional"))
      (node (ref "U3") (pin "50") (pinfunction "PG1_50") (pintype "bidirectional"))
    )
    (net (code "67") (name "/SDRAM_11") (class "Default")
      (node (ref "U2") (pin "35") (pinfunction "A11_35") (pintype "bidirectional"))
      (node (ref "U2") (pin "47") (pinfunction "DQ11_47") (pintype "bidirectional"))
      (node (ref "U3") (pin "49") (pinfunction "PG0_49") (pintype "bidirectional"))
    )
    (net (code "68") (name "/SDRAM_12") (class "Default")
      (node (ref "U2") (pin "36") (pinfunction "A12_36") (pintype "bidirectional"))
      (node (ref "U2") (pin "48") (pinfunction "DQ12_48") (pintype "bidirectional"))
      (node (ref "U3") (pin "75") (pinfunction "PM3_75") (pintype "bidirectional"))
    )
    (net (code "69") (name "/SDRAM_13") (class "Default")
      (node (ref "U2") (pin "20") (pinfunction "BA0_20") (pintype "bidirectional"))
      (node (ref "U2") (pin "50") (pinfunction "DQ13_50") (pintype "bidirectional"))
      (node (ref "U3") (pin "76") (pinfunction "PM2_76") (pintype "bidirectional"))
    )
    (net (code "70") (name "/SDRAM_14") (class "Default")
      (node (ref "U2") (pin "21") (pinfunction "BA1_21") (pintype "bidirectional"))
      (node (ref "U2") (pin "51") (pinfunction "DQ14_51") (pintype "bidirectional"))
      (node (ref "U3") (pin "77") (pinfunction "PM1_77") (pintype "bidirectional"))
    )
    (net (code "71") (name "/SDRAM_15") (class "Default")
      (node (ref "U2") (pin "53") (pinfunction "DQ15_53") (pintype "bidirectional"))
      (node (ref "U3") (pin "78") (pinfunction "PM0_78") (pintype "bidirectional"))
    )
    (net (code "72") (name "/SDRAM_CAS") (class "Default")
      (node (ref "U2") (pin "17") (pinfunction "CAS_17") (pintype "bidirectional"))
      (node (ref "U3") (pin "83") (pinfunction "PL2_83") (pintype "bidirectional"))
    )
    (net (code "73") (name "/SDRAM_CKE") (class "Default")
      (node (ref "U2") (pin "37") (pinfunction "CKE_37") (pintype "bidirectional"))
      (node (ref "U3") (pin "104") (pinfunction "PP3_104") (pintype "bidirectional"))
    )
    (net (code "74") (name "/SDRAM_CLK") (class "Default")
      (node (ref "U2") (pin "38") (pinfunction "CLK_38") (pintype "bidirectional"))
      (node (ref "U3") (pin "62") (pinfunction "PK5_62") (pintype "bidirectional"))
    )
    (net (code "75") (name "/SDRAM_CS") (class "Default")
      (node (ref "U2") (pin "19") (pinfunction "CS_19") (pintype "bidirectional"))
      (node (ref "U3") (pin "103") (pinfunction "PP2_103") (pintype "bidirectional"))
    )
    (net (code "76") (name "/SDRAM_LDQM") (class "Default")
      (node (ref "U2") (pin "15") (pinfunction "DQML_15") (pintype "bidirectional"))
      (node (ref "U3") (pin "81") (pinfunction "PL0_81") (pintype "bidirectional"))
    )
    (net (code "77") (name "/SDRAM_RAS") (class "Default")
      (node (ref "U2") (pin "18") (pinfunction "RAS_18") (pintype "bidirectional"))
      (node (ref "U3") (pin "84") (pinfunction "PL3_84") (pintype "bidirectional"))
    )
    (net (code "78") (name "/SDRAM_UDQM") (class "Default")
      (node (ref "U2") (pin "39") (pinfunction "DQMH_39") (pintype "bidirectional"))
      (node (ref "U3") (pin "82") (pinfunction "PL1_82") (pintype "bidirectional"))
    )
    (net (code "79") (name "/SDRAM_WE") (class "Default")
      (node (ref "U2") (pin "16") (pinfunction "WE_16") (pintype "bidirectional"))
      (node (ref "U3") (pin "92") (pinfunction "PB3_92") (pintype "bidirectional"))
    )
    (net (code "80") (name "/SD_CD") (class "Default")
      (node (ref "U$2") (pin "CD1") (pinfunction "CARD_DETECT_CD1") (pintype "passive"))
      (node (ref "U3") (pin "102") (pinfunction "PQ4_102") (pintype "bidirectional"))
    )
    (net (code "81") (name "/SD_CS") (class "Default")
      (node (ref "U$2") (pin "2") (pinfunction "CS_2") (pintype "input"))
      (node (ref "U3") (pin "38") (pinfunction "PA5_38") (pintype "bidirectional"))
    )
    (net (code "82") (name "/SD_IN") (class "Default")
      (node (ref "U$2") (pin "3") (pinfunction "DATA_IN_3") (pintype "input"))
      (node (ref "U3") (pin "37") (pinfunction "PA4_37") (pintype "bidirectional"))
    )
    (net (code "83") (name "/SWCLK") (class "Default")
      (node (ref "U3") (pin "100") (pinfunction "PC0_TCK_SWCLK_100") (pintype "bidirectional"))
      (node (ref "X1") (pin "4") (pinfunction "S_4") (pintype "passive"))
    )
    (net (code "84") (name "/TDI") (class "Default")
      (node (ref "U3") (pin "98") (pinfunction "PC2_TDI_98") (pintype "bidirectional"))
      (node (ref "X1") (pin "8") (pinfunction "S_8") (pintype "passive"))
    )
    (net (code "85") (name "/TDO_SWO") (class "Default")
      (node (ref "U3") (pin "97") (pinfunction "PC3_TDO_SWO_97") (pintype "bidirectional"))
      (node (ref "X1") (pin "6") (pinfunction "S_6") (pintype "passive"))
    )
    (net (code "86") (name "/TMS_SWDIO") (class "Default")
      (node (ref "U3") (pin "99") (pinfunction "PC1_TMS_SWDIO_99") (pintype "bidirectional"))
      (node (ref "X1") (pin "2") (pinfunction "S_2") (pintype "passive"))
    )
    (net (code "87") (name "1.8V") (class "Default")
      (node (ref "C1") (pin "2") (pinfunction "2_2") (pintype "passive"))
      (node (ref "C2") (pin "2") (pinfunction "2_2") (pintype "passive"))
      (node (ref "C3") (pin "2") (pinfunction "2_2") (pintype "passive"))
      (node (ref "C40") (pin "2") (pinfunction "2_2") (pintype "passive"))
      (node (ref "C41") (pin "2") (pinfunction "2_2") (pintype "passive"))
      (node (ref "C5") (pin "2") (pinfunction "2_2") (pintype "passive"))
      (node (ref "C6") (pin "2") (pinfunction "2_2") (pintype "passive"))
      (node (ref "U$5") (pin "P$5") (pinfunction "V_OUT_P$5") (pintype "bidirectional"))
      (node (ref "U1") (pin "1") (pinfunction "1_1") (pintype "passive"))
      (node (ref "U1") (pin "16") (pinfunction "16_16") (pintype "passive"))
      (node (ref "U1") (pin "19") (pinfunction "19_19") (pintype "passive"))
      (node (ref "U1") (pin "20") (pinfunction "20_20") (pintype "passive"))
      (node (ref "U1") (pin "21") (pinfunction "21_21") (pintype "passive"))
      (node (ref "U1") (pin "24") (pinfunction "24_24") (pintype "passive"))
      (node (ref "U1") (pin "29") (pinfunction "29_29") (pintype "passive"))
      (node (ref "U1") (pin "36") (pinfunction "36_36") (pintype "passive"))
      (node (ref "U1") (pin "41") (pinfunction "41_41") (pintype "passive"))
      (node (ref "U1") (pin "61") (pinfunction "61_61") (pintype "passive"))
      (node (ref "U1") (pin "62") (pinfunction "62_62") (pintype "passive"))
      (node (ref "U1") (pin "63") (pinfunction "63_63") (pintype "passive"))
      (node (ref "U1") (pin "64") (pinfunction "64_64") (pintype "passive"))
    )
    (net (code "88") (name "3.3V") (class "Default")
      (node (ref "C14") (pin "1") (pinfunction "1_1") (pintype "passive"))
      (node (ref "C16") (pin "1") (pinfunction "1_1") (pintype "passive"))
      (node (ref "C17") (pin "1") (pinfunction "1_1") (pintype "passive"))
      (node (ref "C18") (pin "1") (pinfunction "1_1") (pintype "passive"))
      (node (ref "C19") (pin "1") (pinfunction "1_1") (pintype "passive"))
      (node (ref "C20") (pin "1") (pinfunction "1_1") (pintype "passive"))
      (node (ref "C21") (pin "1") (pinfunction "1_1") (pintype "passive"))
      (node (ref "C22") (pin "1") (pinfunction "1_1") (pintype "passive"))
      (node (ref "C23") (pin "1") (pinfunction "1_1") (pintype "passive"))
      (node (ref "C24") (pin "1") (pinfunction "1_1") (pintype "passive"))
      (node (ref "C25") (pin "1") (pinfunction "1_1") (pintype "passive"))
      (node (ref "C26") (pin "1") (pinfunction "1_1") (pintype "passive"))
      (node (ref "C27") (pin "1") (pinfunction "1_1") (pintype "passive"))
      (node (ref "C28") (pin "1") (pinfunction "1_1") (pintype "passive"))
      (node (ref "C31") (pin "1") (pinfunction "1_1") (pintype "passive"))
      (node (ref "C32") (pin "1") (pinfunction "1_1") (pintype "passive"))
      (node (ref "C33") (pin "1") (pinfunction "1_1") (pintype "passive"))
      (node (ref "C34") (pin "1") (pinfunction "1_1") (pintype "passive"))
      (node (ref "C35") (pin "1") (pinfunction "1_1") (pintype "passive"))
      (node (ref "C36") (pin "1") (pinfunction "1_1") (pintype "passive"))
      (node (ref "C44") (pin "1") (pinfunction "1_1") (pintype "passive"))
      (node (ref "C46") (pin "2") (pinfunction "2_2") (pintype "passive"))
      (node (ref "C7") (pin "1") (pinfunction "1_1") (pintype "passive"))
      (node (ref "IC1") (pin "2") (pinfunction "OUT_2") (pintype "output"))
      (node (ref "IC1") (pin "4") (pinfunction "OUT_4") (pintype "output"))
      (node (ref "R23") (pin "1") (pinfunction "1_1") (pintype "passive"))
      (node (ref "R7") (pin "2") (pinfunction "2_2") (pintype "passive"))
      (node (ref "U$1") (pin "19") (pinfunction "PWREN_19") (pintype "bidirectional"))
      (node (ref "U$1") (pin "20") (pinfunction "VDD_20") (pintype "bidirectional"))
      (node (ref "U$2") (pin "4") (pinfunction "VDD_4") (pintype "power_in"))
      (node (ref "U2") (pin "1") (pinfunction "VDD1_1") (pintype "bidirectional"))
      (node (ref "U2") (pin "14") (pinfunction "VDD2_14") (pintype "bidirectional"))
      (node (ref "U2") (pin "27") (pinfunction "VDD3_27") (pintype "bidirectional"))
      (node (ref "U2") (pin "3") (pinfunction "VDDQ1_3") (pintype "bidirectional"))
      (node (ref "U2") (pin "43") (pinfunction "VDDQ3_43") (pintype "bidirectional"))
      (node (ref "U2") (pin "49") (pinfunction "VDDQ4_49") (pintype "bidirectional"))
      (node (ref "U2") (pin "9") (pinfunction "VDDQ2_9") (pintype "bidirectional"))
      (node (ref "U3") (pin "101") (pinfunction "VDD_13_101") (pintype "power_in"))
      (node (ref "U3") (pin "113") (pinfunction "VDD_14_113") (pintype "power_in"))
      (node (ref "U3") (pin "122") (pinfunction "VDD_122") (pintype "power_in"))
      (node (ref "U3") (pin "16") (pinfunction "VDD_3_16") (pintype "power_in"))
      (node (ref "U3") (pin "26") (pinfunction "VDD_4_26") (pintype "power_in"))
      (node (ref "U3") (pin "28") (pinfunction "VDD_5_28") (pintype "power_in"))
      (node (ref "U3") (pin "39") (pinfunction "VDD_6_39") (pintype "power_in"))
      (node (ref "U3") (pin "47") (pinfunction "VDD_7_47") (pintype "power_in"))
      (node (ref "U3") (pin "51") (pinfunction "VDD_8_51") (pintype "power_in"))
      (node (ref "U3") (pin "52") (pinfunction "VDD_9_52") (pintype "power_in"))
      (node (ref "U3") (pin "68") (pinfunction "VBAT_68") (pintype "power_in"))
      (node (ref "U3") (pin "69") (pinfunction "VDD_10_69") (pintype "power_in"))
      (node (ref "U3") (pin "7") (pinfunction "VDD_2_7") (pintype "power_in"))
      (node (ref "U3") (pin "79") (pinfunction "VDD_11_79") (pintype "power_in"))
      (node (ref "U3") (pin "8") (pinfunction "VDDA_8") (pintype "power_in"))
      (node (ref "U3") (pin "9") (pinfunction "VREFA+_9") (pintype "power_in"))
      (node (ref "U3") (pin "90") (pinfunction "VDD_12_90") (pintype "power_in"))
      (node (ref "X1") (pin "1") (pinfunction "S_1") (pintype "passive"))
      (node (ref "X6") (pin "2") (pinfunction "S_2") (pintype "passive"))
    )
    (net (code "89") (name "5V") (class "Default")
      (node (ref "C4") (pin "1") (pinfunction "1_1") (pintype "passive"))
      (node (ref "C43") (pin "P$1") (pinfunction "+_P$1") (pintype "passive"))
      (node (ref "IC1") (pin "3") (pinfunction "IN_3") (pintype "input"))
      (node (ref "R11") (pin "2") (pinfunction "2_2") (pintype "passive"))
      (node (ref "R4") (pin "2") (pinfunction "2_2") (pintype "passive"))
      (node (ref "U$3") (pin "P$18") (pinfunction "VCC_P$18") (pintype "bidirectional"))
      (node (ref "U$4") (pin "P$2") (pinfunction "V_OUT_P$2") (pintype "bidirectional"))
    )
    (net (code "90") (name "GND") (class "Default")
      (node (ref "C1") (pin "1") (pinfunction "1_1") (pintype "passive"))
      (node (ref "C11") (pin "1") (pinfunction "1_1") (pintype "passive"))
      (node (ref "C12") (pin "1") (pinfunction "1_1") (pintype "passive"))
      (node (ref "C13") (pin "1") (pinfunction "1_1") (pintype "passive"))
      (node (ref "C14") (pin "2") (pinfunction "2_2") (pintype "passive"))
      (node (ref "C15") (pin "1") (pinfunction "1_1") (pintype "passive"))
      (node (ref "C16") (pin "2") (pinfunction "2_2") (pintype "passive"))
      (node (ref "C17") (pin "2") (pinfunction "2_2") (pintype "passive"))
      (node (ref "C18") (pin "2") (pinfunction "2_2") (pintype "passive"))
      (node (ref "C19") (pin "2") (pinfunction "2_2") (pintype "passive"))
      (node (ref "C2") (pin "1") (pinfunction "1_1") (pintype "passive"))
      (node (ref "C20") (pin "2") (pinfunction "2_2") (pintype "passive"))
      (node (ref "C21") (pin "2") (pinfunction "2_2") (pintype "passive"))
      (node (ref "C22") (pin "2") (pinfunction "2_2") (pintype "passive"))
      (node (ref "C23") (pin "2") (pinfunction "2_2") (pintype "passive"))
      (node (ref "C24") (pin "2") (pinfunction "2_2") (pintype "passive"))
      (node (ref "C25") (pin "2") (pinfunction "2_2") (pintype "passive"))
      (node (ref "C26") (pin "2") (pinfunction "2_2") (pintype "passive"))
      (node (ref "C27") (pin "2") (pinfunction "2_2") (pintype "passive"))
      (node (ref "C28") (pin "2") (pinfunction "2_2") (pintype "passive"))
      (node (ref "C29") (pin "P$2") (pinfunction "-_P$2") (pintype "passive"))
      (node (ref "C3") (pin "1") (pinfunction "1_1") (pintype "passive"))
      (node (ref "C30") (pin "2") (pinfunction "2_2") (pintype "passive"))
      (node (ref "C31") (pin "2") (pinfunction "2_2") (pintype "passive"))
      (node (ref "C32") (pin "2") (pinfunction "2_2") (pintype "passive"))
      (node (ref "C33") (pin "2") (pinfunction "2_2") (pintype "passive"))
      (node (ref "C34") (pin "2") (pinfunction "2_2") (pintype "passive"))
      (node (ref "C35") (pin "2") (pinfunction "2_2") (pintype "passive"))
      (node (ref "C36") (pin "2") (pinfunction "2_2") (pintype "passive"))
      (node (ref "C37") (pin "2") (pinfunction "2_2") (pintype "passive"))
      (node (ref "C38") (pin "2") (pinfunction "2_2") (pintype "passive"))
      (node (ref "C39") (pin "2") (pinfunction "2_2") (pintype "passive"))
      (node (ref "C4") (pin "2") (pinfunction "2_2") (pintype "passive"))
      (node (ref "C40") (pin "1") (pinfunction "1_1") (pintype "passive"))
      (node (ref "C41") (pin "1") (pinfunction "1_1") (pintype "passive"))
      (node (ref "C42") (pin "P$2") (pinfunction "-_P$2") (pintype "passive"))
      (node (ref "C43") (pin "P$2") (pinfunction "-_P$2") (pintype "passive"))
      (node (ref "C44") (pin "2") (pinfunction "2_2") (pintype "passive"))
      (node (ref "C46") (pin "1") (pinfunction "1_1") (pintype "passive"))
      (node (ref "C48") (pin "2") (pinfunction "2_2") (pintype "passive"))
      (node (ref "C49") (pin "1") (pinfunction "1_1") (pintype "passive"))
      (node (ref "C5") (pin "1") (pinfunction "1_1") (pintype "passive"))
      (node (ref "C50") (pin "1") (pinfunction "1_1") (pintype "passive"))
      (node (ref "C6") (pin "1") (pinfunction "1_1") (pintype "passive"))
      (node (ref "C7") (pin "2") (pinfunction "2_2") (pintype "passive"))
      (node (ref "C9") (pin "1") (pinfunction "1_1") (pintype "passive"))
      (node (ref "IC1") (pin "1") (pinfunction "ADJ_1") (pintype "input"))
      (node (ref "R1") (pin "2") (pinfunction "2_2") (pintype "passive"))
      (node (ref "R12") (pin "2") (pinfunction "2_2") (pintype "passive"))
      (node (ref "R15") (pin "1") (pinfunction "1_1") (pintype "passive"))
      (node (ref "R16") (pin "1") (pinfunction "1_1") (pintype "passive"))
      (node (ref "R21") (pin "1") (pinfunction "1_1") (pintype "passive"))
      (node (ref "R22") (pin "1") (pinfunction "1_1") (pintype "passive"))
      (node (ref "R8") (pin "1") (pinfunction "1_1") (pintype "passive"))
      (node (ref "S1") (pin "3") (pinfunction "3_3") (pintype "passive"))
      (node (ref "S1") (pin "4") (pinfunction "4_4") (pintype "passive"))
      (node (ref "U$1") (pin "G1") (pinfunction "GND9_G1") (pintype "bidirectional"))
      (node (ref "U$1") (pin "G2") (pinfunction "GND8_G2") (pintype "bidirectional"))
      (node (ref "U$1") (pin "G3") (pinfunction "GND7_G3") (pintype "bidirectional"))
      (node (ref "U$1") (pin "G4") (pinfunction "GND6_G4") (pintype "bidirectional"))
      (node (ref "U$1") (pin "RFG1") (pinfunction "GND_RFG1") (pintype "bidirectional"))
      (node (ref "U$1") (pin "RFG2") (pinfunction "GND1_RFG2") (pintype "bidirectional"))
      (node (ref "U$1") (pin "RFG3") (pinfunction "GND2_RFG3") (pintype "bidirectional"))
      (node (ref "U$1") (pin "RFG4") (pinfunction "GND3_RFG4") (pintype "bidirectional"))
      (node (ref "U$1") (pin "RFG5") (pinfunction "GND4_RFG5") (pintype "bidirectional"))
      (node (ref "U$1") (pin "RFG6") (pinfunction "GND5_RFG6") (pintype "bidirectional"))
      (node (ref "U$2") (pin "6") (pinfunction "VSS_6") (pintype "power_in"))
      (node (ref "U$2") (pin "CD2") (pinfunction "CARD_DETECT1_CD2") (pintype "passive"))
      (node (ref "U$2") (pin "MT1") (pinfunction "GND_MT1") (pintype "power_in"))
      (node (ref "U$2") (pin "MT2") (pinfunction "GND1_MT2") (pintype "power_in"))
      (node (ref "U$3") (pin "P$12") (pinfunction "TXCSHLD_P$12") (pintype "bidirectional"))
      (node (ref "U$3") (pin "P$17") (pinfunction "P$17_P$17") (pintype "bidirectional"))
      (node (ref "U$3") (pin "P$2") (pinfunction "TX2SHLD_P$2") (pintype "bidirectional"))
      (node (ref "U$3") (pin "P$5") (pinfunction "TX1SHLD_P$5") (pintype "bidirectional"))
      (node (ref "U$3") (pin "P$8") (pinfunction "TX0SHLD_P$8") (pintype "bidirectional"))
      (node (ref "U$4") (pin "P$1") (pinfunction "GND_P$1") (pintype "bidirectional"))
      (node (ref "U$5") (pin "P$3") (pinfunction "GND_P$3") (pintype "bidirectional"))
      (node (ref "U$7") (pin "5") (pinfunction "GND_5") (pintype "bidirectional"))
      (node (ref "U1") (pin "10") (pinfunction "10_10") (pintype "passive"))
      (node (ref "U1") (pin "11") (pinfunction "11_11") (pintype "passive"))
      (node (ref "U1") (pin "12") (pinfunction "12_12") (pintype "passive"))
      (node (ref "U1") (pin "13") (pinfunction "13_13") (pintype "passive"))
      (node (ref "U1") (pin "14") (pinfunction "14_14") (pintype "passive"))
      (node (ref "U1") (pin "15") (pinfunction "15_15") (pintype "passive"))
      (node (ref "U1") (pin "17") (pinfunction "17_17") (pintype "passive"))
      (node (ref "U1") (pin "18") (pinfunction "18_18") (pintype "passive"))
      (node (ref "U1") (pin "22") (pinfunction "22_22") (pintype "passive"))
      (node (ref "U1") (pin "26") (pinfunction "26_26") (pintype "passive"))
      (node (ref "U1") (pin "32") (pinfunction "32_32") (pintype "passive"))
      (node (ref "U1") (pin "39") (pinfunction "39_39") (pintype "passive"))
      (node (ref "U1") (pin "42") (pinfunction "42_42") (pintype "passive"))
      (node (ref "U1") (pin "43") (pinfunction "43_43") (pintype "passive"))
      (node (ref "U1") (pin "59") (pinfunction "59_59") (pintype "passive"))
      (node (ref "U1") (pin "60") (pinfunction "60_60") (pintype "passive"))
      (node (ref "U1") (pin "7") (pinfunction "7_7") (pintype "passive"))
      (node (ref "U1") (pin "79") (pinfunction "79_79") (pintype "passive"))
      (node (ref "U1") (pin "8") (pinfunction "8_8") (pintype "passive"))
      (node (ref "U1") (pin "80") (pinfunction "80_80") (pintype "passive"))
      (node (ref "U1") (pin "9") (pinfunction "9_9") (pintype "passive"))
      (node (ref "U2") (pin "12") (pinfunction "VSSQ2_12") (pintype "bidirectional"))
      (node (ref "U2") (pin "28") (pinfunction "VSS1_28") (pintype "bidirectional"))
      (node (ref "U2") (pin "41") (pinfunction "VSS2_41") (pintype "bidirectional"))
      (node (ref "U2") (pin "46") (pinfunction "VSSQ3_46") (pintype "bidirectional"))
      (node (ref "U2") (pin "52") (pinfunction "VSSQ4_52") (pintype "bidirectional"))
      (node (ref "U2") (pin "54") (pinfunction "VSS3_54") (pintype "bidirectional"))
      (node (ref "U2") (pin "6") (pinfunction "VSSQ1_6") (pintype "bidirectional"))
      (node (ref "U3") (pin "10") (pinfunction "GNDA_10") (pintype "power_in"))
      (node (ref "U3") (pin "114") (pinfunction "GND_114") (pintype "power_in"))
      (node (ref "U3") (pin "17") (pinfunction "GND_2_17") (pintype "power_in"))
      (node (ref "U3") (pin "48") (pinfunction "GND_3_48") (pintype "power_in"))
      (node (ref "U3") (pin "55") (pinfunction "GND_4_55") (pintype "power_in"))
      (node (ref "U3") (pin "58") (pinfunction "GND_5_58") (pintype "power_in"))
      (node (ref "U3") (pin "80") (pinfunction "GND_6_80") (pintype "power_in"))
      (node (ref "U4") (pin "GND") (pinfunction "GND_GND") (pintype "bidirectional"))
      (node (ref "U5") (pin "2") (pinfunction "VSS_2") (pintype "power_in"))
      (node (ref "X1") (pin "3") (pinfunction "S_3") (pintype "passive"))
      (node (ref "X1") (pin "5") (pinfunction "S_5") (pintype "passive"))
      (node (ref "X1") (pin "9") (pinfunction "S_9") (pintype "passive"))
      (node (ref "X4") (pin "2") (pinfunction "S_2") (pintype "passive"))
      (node (ref "X6") (pin "6") (pinfunction "S_6") (pintype "passive"))
      (node (ref "X7") (pin "3") (pinfunction "S_3") (pintype "passive"))
      (node (ref "X7") (pin "4") (pinfunction "S_4") (pintype "passive"))
      (node (ref "X8") (pin "1") (pinfunction "S_1") (pintype "passive"))
    )
    (net (code "91") (name "Net-(C29-+)") (class "Default")
      (node (ref "C29") (pin "P$1") (pinfunction "+_P$1") (pintype "passive"))
      (node (ref "R6") (pin "1") (pinfunction "1_1") (pintype "passive"))
      (node (ref "R7") (pin "1") (pinfunction "1_1") (pintype "passive"))
      (node (ref "U3") (pin "70") (pinfunction "RST_N_70") (pintype "input"))
    )
    (net (code "92") (name "Net-(D1-PadA)") (class "Default")
      (node (ref "D1") (pin "A") (pinfunction "A_A") (pintype "passive"))
      (node (ref "R9") (pin "2") (pinfunction "2_2") (pintype "passive"))
    )
    (net (code "93") (name "Net-(IC2A-I0)") (class "Default")
      (node (ref "C50") (pin "2") (pinfunction "2_2") (pintype "passive"))
      (node (ref "IC2") (pin "1") (pinfunction "I0_1") (pintype "input"))
      (node (ref "R17") (pin "1") (pinfunction "1_1") (pintype "passive"))
    )
    (net (code "94") (name "Net-(IC2A-O)") (class "Default")
      (node (ref "IC2") (pin "4") (pinfunction "O_4") (pintype "output"))
      (node (ref "IC3") (pin "2") (pinfunction "I1_2") (pintype "input"))
    )
    (net (code "95") (name "Net-(IC3A-I0)") (class "Default")
      (node (ref "C47") (pin "1") (pinfunction "1_1") (pintype "passive"))
      (node (ref "IC3") (pin "1") (pinfunction "I0_1") (pintype "input"))
      (node (ref "R18") (pin "1") (pinfunction "1_1") (pintype "passive"))
    )
    (net (code "96") (name "Net-(R1-Pad1)") (class "Default")
      (node (ref "R1") (pin "1") (pinfunction "1_1") (pintype "passive"))
      (node (ref "U1") (pin "23") (pinfunction "23_23") (pintype "passive"))
    )
    (net (code "97") (name "Net-(R6-Pad2)") (class "Default")
      (node (ref "R6") (pin "2") (pinfunction "2_2") (pintype "passive"))
      (node (ref "S1") (pin "1") (pinfunction "1_1") (pintype "passive"))
      (node (ref "S1") (pin "2") (pinfunction "2_2") (pintype "passive"))
    )
    (net (code "98") (name "Net-(U$1-AGND)") (class "Default")
      (node (ref "R16") (pin "2") (pinfunction "2_2") (pintype "passive"))
      (node (ref "U$1") (pin "36") (pinfunction "AGND_36") (pintype "bidirectional"))
    )
    (net (code "99") (name "Net-(U$1-MIC_BIAS)") (class "Default")
      (node (ref "C10") (pin "1") (pinfunction "1_1") (pintype "passive"))
      (node (ref "C11") (pin "2") (pinfunction "2_2") (pintype "passive"))
      (node (ref "R3") (pin "1") (pinfunction "1_1") (pintype "passive"))
      (node (ref "U$1") (pin "31") (pinfunction "MIC_BIAS_31") (pintype "bidirectional"))
    )
    (net (code "100") (name "Net-(U$1-MIC_R+)") (class "Default")
      (node (ref "C10") (pin "2") (pinfunction "2_2") (pintype "passive"))
      (node (ref "U$1") (pin "33") (pinfunction "MIC_R+_33") (pintype "bidirectional"))
    )
    (net (code "101") (name "Net-(U$1-MIC_R-)") (class "Default")
      (node (ref "C8") (pin "2") (pinfunction "2_2") (pintype "passive"))
      (node (ref "U$1") (pin "35") (pinfunction "MIC_R-_35") (pintype "bidirectional"))
    )
    (net (code "102") (name "Net-(U$1-SPKR_L+)") (class "Default")
      (node (ref "R13") (pin "2") (pinfunction "2_2") (pintype "passive"))
      (node (ref "U$1") (pin "40") (pinfunction "SPKR_L+_40") (pintype "bidirectional"))
    )
    (net (code "103") (name "Net-(U$1-SPKR_L-)") (class "Default")
      (node (ref "R2") (pin "2") (pinfunction "2_2") (pintype "passive"))
      (node (ref "U$1") (pin "38") (pinfunction "SPKR_L-_38") (pintype "bidirectional"))
    )
    (net (code "104") (name "Net-(U$1-SPKR_R+)") (class "Default")
      (node (ref "R5") (pin "2") (pinfunction "2_2") (pintype "passive"))
      (node (ref "U$1") (pin "39") (pinfunction "SPKR_R+_39") (pintype "bidirectional"))
    )
    (net (code "105") (name "Net-(U$1-SPKR_R-)") (class "Default")
      (node (ref "R14") (pin "2") (pinfunction "2_2") (pintype "passive"))
      (node (ref "U$1") (pin "37") (pinfunction "SPKR_R-_37") (pintype "bidirectional"))
    )
    (net (code "106") (name "Net-(U$2-SCLK)") (class "Default")
      (node (ref "U$2") (pin "5") (pinfunction "SCLK_5") (pintype "input"))
      (node (ref "U3") (pin "63") (pinfunction "PK4_63") (pintype "bidirectional"))
    )
    (net (code "107") (name "Net-(U$3-HPD)") (class "Default")
      (node (ref "R12") (pin "1") (pinfunction "1_1") (pintype "passive"))
      (node (ref "U$3") (pin "P$19") (pinfunction "HPD_P$19") (pintype "bidirectional"))
      (node (ref "U1") (pin "25") (pinfunction "25_25") (pintype "passive"))
    )
    (net (code "108") (name "Net-(U$3-TX0+)") (class "Default")
      (node (ref "U$3") (pin "P$7") (pinfunction "TX0+_P$7") (pintype "bidirectional"))
      (node (ref "U1") (pin "31") (pinfunction "31_31") (pintype "passive"))
    )
    (net (code "109") (name "Net-(U$3-TX0-)") (class "Default")
      (node (ref "U$3") (pin "P$9") (pinfunction "TX0-_P$9") (pintype "bidirectional"))
      (node (ref "U1") (pin "30") (pinfunction "30_30") (pintype "passive"))
    )
    (net (code "110") (name "Net-(U$3-TX1+)") (class "Default")
      (node (ref "U$3") (pin "P$4") (pinfunction "TX1+_P$4") (pintype "bidirectional"))
      (node (ref "U1") (pin "35") (pinfunction "35_35") (pintype "passive"))
    )
    (net (code "111") (name "Net-(U$3-TX1-)") (class "Default")
      (node (ref "U$3") (pin "P$6") (pinfunction "TX1-_P$6") (pintype "bidirectional"))
      (node (ref "U1") (pin "34") (pinfunction "34_34") (pintype "passive"))
    )
    (net (code "112") (name "Net-(U$3-TX2+)") (class "Default")
      (node (ref "U$3") (pin "P$1") (pinfunction "TX2+_P$1") (pintype "bidirectional"))
      (node (ref "U1") (pin "38") (pinfunction "38_38") (pintype "passive"))
    )
    (net (code "113") (name "Net-(U$3-TX2-)") (class "Default")
      (node (ref "U$3") (pin "P$3") (pinfunction "TX2-_P$3") (pintype "bidirectional"))
      (node (ref "U1") (pin "37") (pinfunction "37_37") (pintype "passive"))
    )
    (net (code "114") (name "Net-(U$3-TXC+)") (class "Default")
      (node (ref "U$3") (pin "P$10") (pinfunction "TXC+_P$10") (pintype "bidirectional"))
      (node (ref "U1") (pin "28") (pinfunction "28_28") (pintype "passive"))
    )
    (net (code "115") (name "Net-(U$3-TXC-)") (class "Default")
      (node (ref "U$3") (pin "P$11") (pinfunction "TXC-_P$11") (pintype "bidirectional"))
      (node (ref "U1") (pin "27") (pinfunction "27_27") (pintype "passive"))
    )
    (net (code "116") (name "Net-(U$5-TRIM)") (class "Default")
      (node (ref "R15") (pin "2") (pinfunction "2_2") (pintype "passive"))
      (node (ref "U$5") (pin "P$4") (pinfunction "TRIM_P$4") (pintype "bidirectional"))
    )
    (net (code "117") (name "Net-(U$7-CG)") (class "Default")
      (node (ref "R22") (pin "2") (pinfunction "2_2") (pintype "passive"))
      (node (ref "U$7") (pin "6") (pinfunction "CG_6") (pintype "bidirectional"))
      (node (ref "X5") (pin "2") (pinfunction "S_2") (pintype "passive"))
    )
    (net (code "118") (name "Net-(U$7-ROSC)") (class "Default")
      (node (ref "R21") (pin "2") (pinfunction "2_2") (pintype "passive"))
      (node (ref "U$7") (pin "2") (pinfunction "ROSC_2") (pintype "bidirectional"))
    )
    (net (code "119") (name "Net-(U$7-VCC)") (class "Default")
      (node (ref "C37") (pin "1") (pinfunction "1_1") (pintype "passive"))
      (node (ref "C48") (pin "1") (pinfunction "1_1") (pintype "passive"))
      (node (ref "R18") (pin "2") (pinfunction "2_2") (pintype "passive"))
      (node (ref "R19") (pin "1") (pinfunction "1_1") (pintype "passive"))
      (node (ref "R20") (pin "2") (pinfunction "2_2") (pintype "passive"))
      (node (ref "U$7") (pin "7") (pinfunction "VCC_7") (pintype "bidirectional"))
      (node (ref "U5") (pin "3") (pinfunction "VBAT_3") (pintype "power_in"))
      (node (ref "X5") (pin "1") (pinfunction "S_1") (pintype "passive"))
    )
    (net (code "120") (name "Net-(U$7-VIN)") (class "Default")
      (node (ref "C49") (pin "2") (pinfunction "2_2") (pintype "passive"))
      (node (ref "R20") (pin "1") (pinfunction "1_1") (pintype "passive"))
      (node (ref "U$7") (pin "8") (pinfunction "VIN_8") (pintype "bidirectional"))
    )
    (net (code "121") (name "Net-(U3C-OSC0)") (class "Default")
      (node (ref "C39") (pin "1") (pinfunction "1_1") (pintype "passive"))
      (node (ref "U3") (pin "88") (pinfunction "OSC0_88") (pintype "input"))
      (node (ref "Y1") (pin "P$2") (pinfunction "2_P$2") (pintype "passive"))
    )
    (net (code "122") (name "Net-(U3C-OSC1)") (class "Default")
      (node (ref "R10") (pin "2") (pinfunction "2_2") (pintype "passive"))
      (node (ref "U3") (pin "89") (pinfunction "OSC1_89") (pintype "output"))
    )
    (net (code "123") (name "Net-(U3D-VDDC)") (class "Default")
      (node (ref "C12") (pin "2") (pinfunction "2_2") (pintype "passive"))
      (node (ref "C13") (pin "2") (pinfunction "2_2") (pintype "passive"))
      (node (ref "C15") (pin "2") (pinfunction "2_2") (pintype "passive"))
      (node (ref "C9") (pin "2") (pinfunction "2_2") (pintype "passive"))
      (node (ref "U3") (pin "115") (pinfunction "VDDC_115") (pintype "power_in"))
      (node (ref "U3") (pin "87") (pinfunction "VDDC_2_87") (pintype "power_in"))
    )
    (net (code "124") (name "Net-(U5-PROG)") (class "Default")
      (node (ref "R8") (pin "2") (pinfunction "2_2") (pintype "passive"))
      (node (ref "U5") (pin "5") (pinfunction "PROG_5") (pintype "input"))
    )
    (net (code "125") (name "Net-(U5-STAT)") (class "Default")
      (node (ref "D1") (pin "C") (pinfunction "C_C") (pintype "passive"))
      (node (ref "U5") (pin "1") (pinfunction "STAT_1") (pintype "output"))
    )
    (net (code "126") (name "Net-(U5-VIN)") (class "Default")
      (node (ref "C30") (pin "1") (pinfunction "1_1") (pintype "passive"))
      (node (ref "R9") (pin "1") (pinfunction "1_1") (pintype "passive"))
      (node (ref "U4") (pin "VBUS") (pinfunction "VBUS_VBUS") (pintype "bidirectional"))
      (node (ref "U5") (pin "4") (pinfunction "VIN_4") (pintype "power_in"))
    )
    (net (code "127") (name "Net-(X2A-S)") (class "Default")
      (node (ref "R13") (pin "1") (pinfunction "1_1") (pintype "passive"))
      (node (ref "X2") (pin "1") (pinfunction "S_1") (pintype "passive"))
    )
    (net (code "128") (name "Net-(X2B-S)") (class "Default")
      (node (ref "R2") (pin "1") (pinfunction "1_1") (pintype "passive"))
      (node (ref "X2") (pin "2") (pinfunction "S_2") (pintype "passive"))
    )
    (net (code "129") (name "Net-(X3A-S)") (class "Default")
      (node (ref "R5") (pin "1") (pinfunction "1_1") (pintype "passive"))
      (node (ref "X3") (pin "1") (pinfunction "S_1") (pintype "passive"))
    )
    (net (code "130") (name "Net-(X3B-S)") (class "Default")
      (node (ref "R14") (pin "1") (pinfunction "1_1") (pintype "passive"))
      (node (ref "X3") (pin "2") (pinfunction "S_2") (pintype "passive"))
    )
    (net (code "131") (name "Net-(X4A-S)") (class "Default")
      (node (ref "C8") (pin "1") (pinfunction "1_1") (pintype "passive"))
      (node (ref "R3") (pin "2") (pinfunction "2_2") (pintype "passive"))
      (node (ref "X4") (pin "1") (pinfunction "S_1") (pintype "passive"))
    )
    (net (code "132") (name "Net-(X6O-S)") (class "Default")
      (node (ref "R23") (pin "2") (pinfunction "2_2") (pintype "passive"))
      (node (ref "X6") (pin "4") (pinfunction "S_4") (pintype "passive"))
    )
    (net (code "133") (name "Net-(X8B-S)") (class "Default")
      (node (ref "C47") (pin "2") (pinfunction "2_2") (pintype "passive"))
      (node (ref "R17") (pin "2") (pinfunction "2_2") (pintype "passive"))
      (node (ref "R19") (pin "2") (pinfunction "2_2") (pintype "passive"))
      (node (ref "X8") (pin "2") (pinfunction "S_2") (pintype "passive"))
    )
    (net (code "134") (name "Net-(Y1-1)") (class "Default")
      (node (ref "C38") (pin "1") (pinfunction "1_1") (pintype "passive"))
      (node (ref "R10") (pin "1") (pinfunction "1_1") (pintype "passive"))
      (node (ref "Y1") (pin "P$1") (pinfunction "1_P$1") (pintype "passive"))
    )
    (net (code "135") (name "unconnected-(U$1-AIC0-Pad3)") (class "Default")
      (node (ref "U$1") (pin "3") (pinfunction "AIC0_3") (pintype "bidirectional"))
    )
    (net (code "136") (name "unconnected-(U$1-GPIO2-Pad2)") (class "Default")
      (node (ref "U$1") (pin "2") (pinfunction "GPIO2_2") (pintype "bidirectional"))
    )
    (net (code "137") (name "unconnected-(U$1-GPIO3-Pad1)") (class "Default")
      (node (ref "U$1") (pin "1") (pinfunction "GPIO3_1") (pintype "bidirectional"))
    )
    (net (code "138") (name "unconnected-(U$1-GPIO4-Pad4)") (class "Default")
      (node (ref "U$1") (pin "4") (pinfunction "GPIO4_4") (pintype "bidirectional"))
    )
    (net (code "139") (name "unconnected-(U$1-GPIO5-Pad5)") (class "Default")
      (node (ref "U$1") (pin "5") (pinfunction "GPIO5_5") (pintype "bidirectional"))
    )
    (net (code "140") (name "unconnected-(U$1-GPIO6-Pad18)") (class "Default")
      (node (ref "U$1") (pin "18") (pinfunction "GPIO6_18") (pintype "bidirectional"))
    )
    (net (code "141") (name "unconnected-(U$1-GPIO10-Pad9)") (class "Default")
      (node (ref "U$1") (pin "9") (pinfunction "GPIO10_9") (pintype "bidirectional"))
    )
    (net (code "142") (name "unconnected-(U$1-GPIO11-Pad8)") (class "Default")
      (node (ref "U$1") (pin "8") (pinfunction "GPIO11_8") (pintype "bidirectional"))
    )
    (net (code "143") (name "unconnected-(U$1-GPIO12-Pad6)") (class "Default")
      (node (ref "U$1") (pin "6") (pinfunction "GPIO12_6") (pintype "bidirectional"))
    )
    (net (code "144") (name "unconnected-(U$1-GPIO13-Pad7)") (class "Default")
      (node (ref "U$1") (pin "7") (pinfunction "GPIO13_7") (pintype "bidirectional"))
    )
    (net (code "145") (name "unconnected-(U$1-LED0-Pad30)") (class "Default")
      (node (ref "U$1") (pin "30") (pinfunction "LED0_30") (pintype "bidirectional"))
    )
    (net (code "146") (name "unconnected-(U$1-LED1-Pad29)") (class "Default")
      (node (ref "U$1") (pin "29") (pinfunction "LED1_29") (pintype "bidirectional"))
    )
    (net (code "147") (name "unconnected-(U$1-MIC_L+-Pad32)") (class "Default")
      (node (ref "U$1") (pin "32") (pinfunction "MIC_L+_32") (pintype "bidirectional"))
    )
    (net (code "148") (name "unconnected-(U$1-MIC_L--Pad34)") (class "Default")
      (node (ref "U$1") (pin "34") (pinfunction "MIC_L-_34") (pintype "bidirectional"))
    )
    (net (code "149") (name "unconnected-(U$1-PCM_CLK-Pad24)") (class "Default")
      (node (ref "U$1") (pin "24") (pinfunction "PCM_CLK_24") (pintype "bidirectional"))
    )
    (net (code "150") (name "unconnected-(U$1-PCM_IN-Pad21)") (class "Default")
      (node (ref "U$1") (pin "21") (pinfunction "PCM_IN_21") (pintype "bidirectional"))
    )
    (net (code "151") (name "unconnected-(U$1-PCM_OUT-Pad22)") (class "Default")
      (node (ref "U$1") (pin "22") (pinfunction "PCM_OUT_22") (pintype "bidirectional"))
    )
    (net (code "152") (name "unconnected-(U$1-PCM_SYNC-Pad23)") (class "Default")
      (node (ref "U$1") (pin "23") (pinfunction "PCM_SYNC_23") (pintype "bidirectional"))
    )
    (net (code "153") (name "unconnected-(U$1-SPI_CLK-Pad27)") (class "Default")
      (node (ref "U$1") (pin "27") (pinfunction "SPI_CLK_27") (pintype "bidirectional"))
    )
    (net (code "154") (name "unconnected-(U$1-SPI_MISO-Pad26)") (class "Default")
      (node (ref "U$1") (pin "26") (pinfunction "SPI_MISO_26") (pintype "bidirectional"))
    )
    (net (code "155") (name "unconnected-(U$1-SPI_MOSI-Pad28)") (class "Default")
      (node (ref "U$1") (pin "28") (pinfunction "SPI_MOSI_28") (pintype "bidirectional"))
    )
    (net (code "156") (name "unconnected-(U$1-SPI_SS-Pad25)") (class "Default")
      (node (ref "U$1") (pin "25") (pinfunction "SPI_SS_25") (pintype "bidirectional"))
    )
    (net (code "157") (name "unconnected-(U$1-USBD+-Pad12)") (class "Default")
      (node (ref "U$1") (pin "12") (pinfunction "USBD+_12") (pintype "bidirectional"))
    )
    (net (code "158") (name "unconnected-(U$1-USBD--Pad11)") (class "Default")
      (node (ref "U$1") (pin "11") (pinfunction "USBD-_11") (pintype "bidirectional"))
    )
    (net (code "159") (name "unconnected-(U$2-DAT1-Pad8)") (class "Default")
      (node (ref "U$2") (pin "8") (pinfunction "DAT1_8") (pintype "bidirectional"))
    )
    (net (code "160") (name "unconnected-(U$2-DAT2-Pad1)") (class "Default")
      (node (ref "U$2") (pin "1") (pinfunction "DAT2_1") (pintype "bidirectional"))
    )
    (net (code "161") (name "unconnected-(U$2-DATA_OUT-Pad7)") (class "Default")
      (node (ref "U$2") (pin "7") (pinfunction "DATA_OUT_7") (pintype "output"))
    )
    (net (code "162") (name "unconnected-(U$3-CEC-PadP$13)") (class "Default")
      (node (ref "U$3") (pin "P$13") (pinfunction "CEC_P$13") (pintype "bidirectional"))
    )
    (net (code "163") (name "unconnected-(U$3-PadP$14)") (class "Default")
      (node (ref "U$3") (pin "P$14") (pinfunction "P$14_P$14") (pintype "bidirectional"))
    )
    (net (code "164") (name "unconnected-(U$4-V_OUT_ADJUST-PadP$3)") (class "Default")
      (node (ref "U$4") (pin "P$3") (pinfunction "V_OUT_ADJUST_P$3") (pintype "bidirectional"))
    )
    (net (code "165") (name "unconnected-(U$5-ON{slash}OFF-PadP$1)") (class "Default")
      (node (ref "U$5") (pin "P$1") (pinfunction "ON/OFF_P$1") (pintype "bidirectional"))
    )
    (net (code "166") (name "unconnected-(U$7-IO0-Pad1)") (class "Default")
      (node (ref "U$7") (pin "1") (pinfunction "IO0_1") (pintype "bidirectional"))
    )
    (net (code "167") (name "unconnected-(U1-Pad4)") (class "Default")
      (node (ref "U1") (pin "4") (pinfunction "4_4") (pintype "passive"))
    )
    (net (code "168") (name "unconnected-(U1-Pad5)") (class "Default")
      (node (ref "U1") (pin "5") (pinfunction "5_5") (pintype "passive"))
    )
    (net (code "169") (name "unconnected-(U1-Pad33)") (class "Default")
      (node (ref "U1") (pin "33") (pinfunction "33_33") (pintype "passive"))
    )
    (net (code "170") (name "unconnected-(U1-Pad46)") (class "Default")
      (node (ref "U1") (pin "46") (pinfunction "46_46") (pintype "passive"))
    )
    (net (code "171") (name "unconnected-(U1-Pad47)") (class "Default")
      (node (ref "U1") (pin "47") (pinfunction "47_47") (pintype "passive"))
    )
    (net (code "172") (name "unconnected-(U1-Pad48)") (class "Default")
      (node (ref "U1") (pin "48") (pinfunction "48_48") (pintype "passive"))
    )
    (net (code "173") (name "unconnected-(U1-Pad49)") (class "Default")
      (node (ref "U1") (pin "49") (pinfunction "49_49") (pintype "passive"))
    )
    (net (code "174") (name "unconnected-(U2-NC-Pad40)") (class "Default")
      (node (ref "U2") (pin "40") (pinfunction "NC_40") (pintype "bidirectional"))
    )
    (net (code "175") (name "unconnected-(U3A-PB2-Pad91)") (class "Default")
      (node (ref "U3") (pin "91") (pinfunction "PB2_91") (pintype "bidirectional"))
    )
    (net (code "176") (name "unconnected-(U3A-PD1-Pad2)") (class "Default")
      (node (ref "U3") (pin "2") (pinfunction "PD1_2") (pintype "bidirectional"))
    )
    (net (code "177") (name "unconnected-(U3A-PJ1-Pad117)") (class "Default")
      (node (ref "U3") (pin "117") (pinfunction "PJ1_117") (pintype "bidirectional"))
    )
    (net (code "178") (name "unconnected-(U3B-PL6-Pad94)") (class "Default")
      (node (ref "U3") (pin "94") (pinfunction "PL6_94") (pintype "bidirectional"))
    )
    (net (code "179") (name "unconnected-(U3B-PL7-Pad93)") (class "Default")
      (node (ref "U3") (pin "93") (pinfunction "PL7_93") (pintype "bidirectional"))
    )
    (net (code "180") (name "unconnected-(U3B-PP4-Pad105)") (class "Default")
      (node (ref "U3") (pin "105") (pinfunction "PP4_105") (pintype "bidirectional"))
    )
    (net (code "181") (name "unconnected-(U3C-EN0RXIN-Pad53)") (class "Default")
      (node (ref "U3") (pin "53") (pinfunction "EN0RXIN_53") (pintype "bidirectional"))
    )
    (net (code "182") (name "unconnected-(U3C-EN0RXIP-Pad54)") (class "Default")
      (node (ref "U3") (pin "54") (pinfunction "EN0RXIP_54") (pintype "bidirectional"))
    )
    (net (code "183") (name "unconnected-(U3C-EN0TXON-Pad56)") (class "Default")
      (node (ref "U3") (pin "56") (pinfunction "EN0TXON_56") (pintype "bidirectional"))
    )
    (net (code "184") (name "unconnected-(U3C-EN0TXOP-Pad57)") (class "Default")
      (node (ref "U3") (pin "57") (pinfunction "EN0TXOP_57") (pintype "bidirectional"))
    )
    (net (code "185") (name "unconnected-(U3C-HIB_N-Pad65)") (class "Default")
      (node (ref "U3") (pin "65") (pinfunction "HIB_N_65") (pintype "output"))
    )
    (net (code "186") (name "unconnected-(U3C-RBIAS-Pad59)") (class "Default")
      (node (ref "U3") (pin "59") (pinfunction "RBIAS_59") (pintype "output"))
    )
    (net (code "187") (name "unconnected-(U3C-WAKE_N-Pad64)") (class "Default")
      (node (ref "U3") (pin "64") (pinfunction "WAKE_N_64") (pintype "input"))
    )
    (net (code "188") (name "unconnected-(U3C-XOSC0-Pad66)") (class "Default")
      (node (ref "U3") (pin "66") (pinfunction "XOSC0_66") (pintype "input"))
    )
    (net (code "189") (name "unconnected-(U3C-XOSC1-Pad67)") (class "Default")
      (node (ref "U3") (pin "67") (pinfunction "XOSC1_67") (pintype "output"))
    )
    (net (code "190") (name "unconnected-(U4-PadD+)") (class "Default")
      (node (ref "U4") (pin "D+") (pinfunction "D+_D+") (pintype "bidirectional"))
    )
    (net (code "191") (name "unconnected-(U4-PadD-)") (class "Default")
      (node (ref "U4") (pin "D-") (pinfunction "D-_D-") (pintype "bidirectional"))
    )
    (net (code "192") (name "unconnected-(U4-USBID-PadID)") (class "Default")
      (node (ref "U4") (pin "ID") (pinfunction "USBID_ID") (pintype "bidirectional"))
    )
    (net (code "193") (name "unconnected-(X1B-S-Pad10)") (class "Default")
      (node (ref "X1") (pin "10") (pinfunction "S_10") (pintype "passive"))
    )
    (net (code "194") (name "unconnected-(X1H-S-Pad7)") (class "Default")
      (node (ref "X1") (pin "7") (pinfunction "S_7") (pintype "passive"))
    )
    (net (code "195") (name "unconnected-(X5C-S-Pad3)") (class "Default")
      (node (ref "X5") (pin "3") (pinfunction "S_3") (pintype "passive"))
    )
    (net (code "196") (name "unconnected-(X5D-S-Pad4)") (class "Default")
      (node (ref "X5") (pin "4") (pinfunction "S_4") (pintype "passive"))
    )
    (net (code "197") (name "unconnected-(X6B-S-Pad10)") (class "Default")
      (node (ref "X6") (pin "10") (pinfunction "S_10") (pintype "passive"))
    )
    (net (code "198") (name "unconnected-(X6S-S-Pad8)") (class "Default")
      (node (ref "X6") (pin "8") (pinfunction "S_8") (pintype "passive"))
    )
  )
)
